# currentBaseBoard_v5.net
KiCad netlist of a schematic drawn in EAGLE
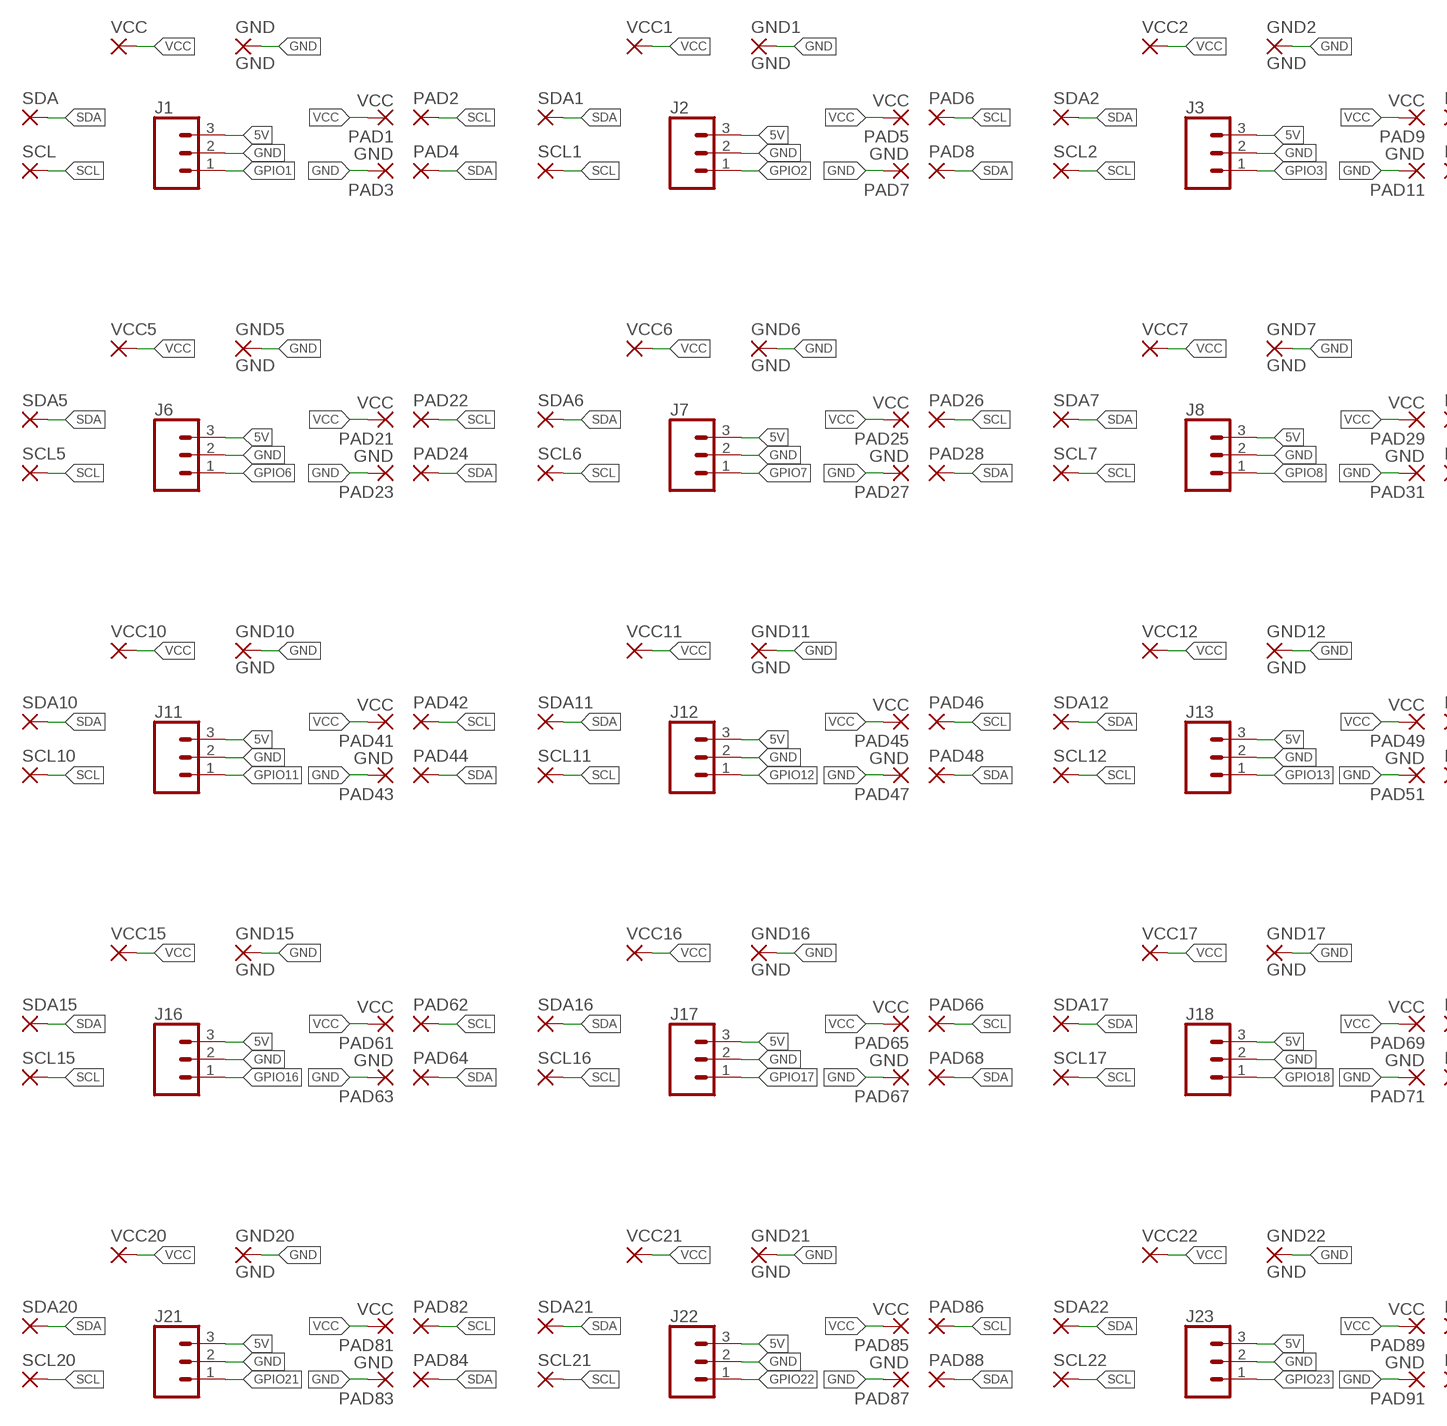
[diagram p0: schematic, sheet 1, part 1 of 2]
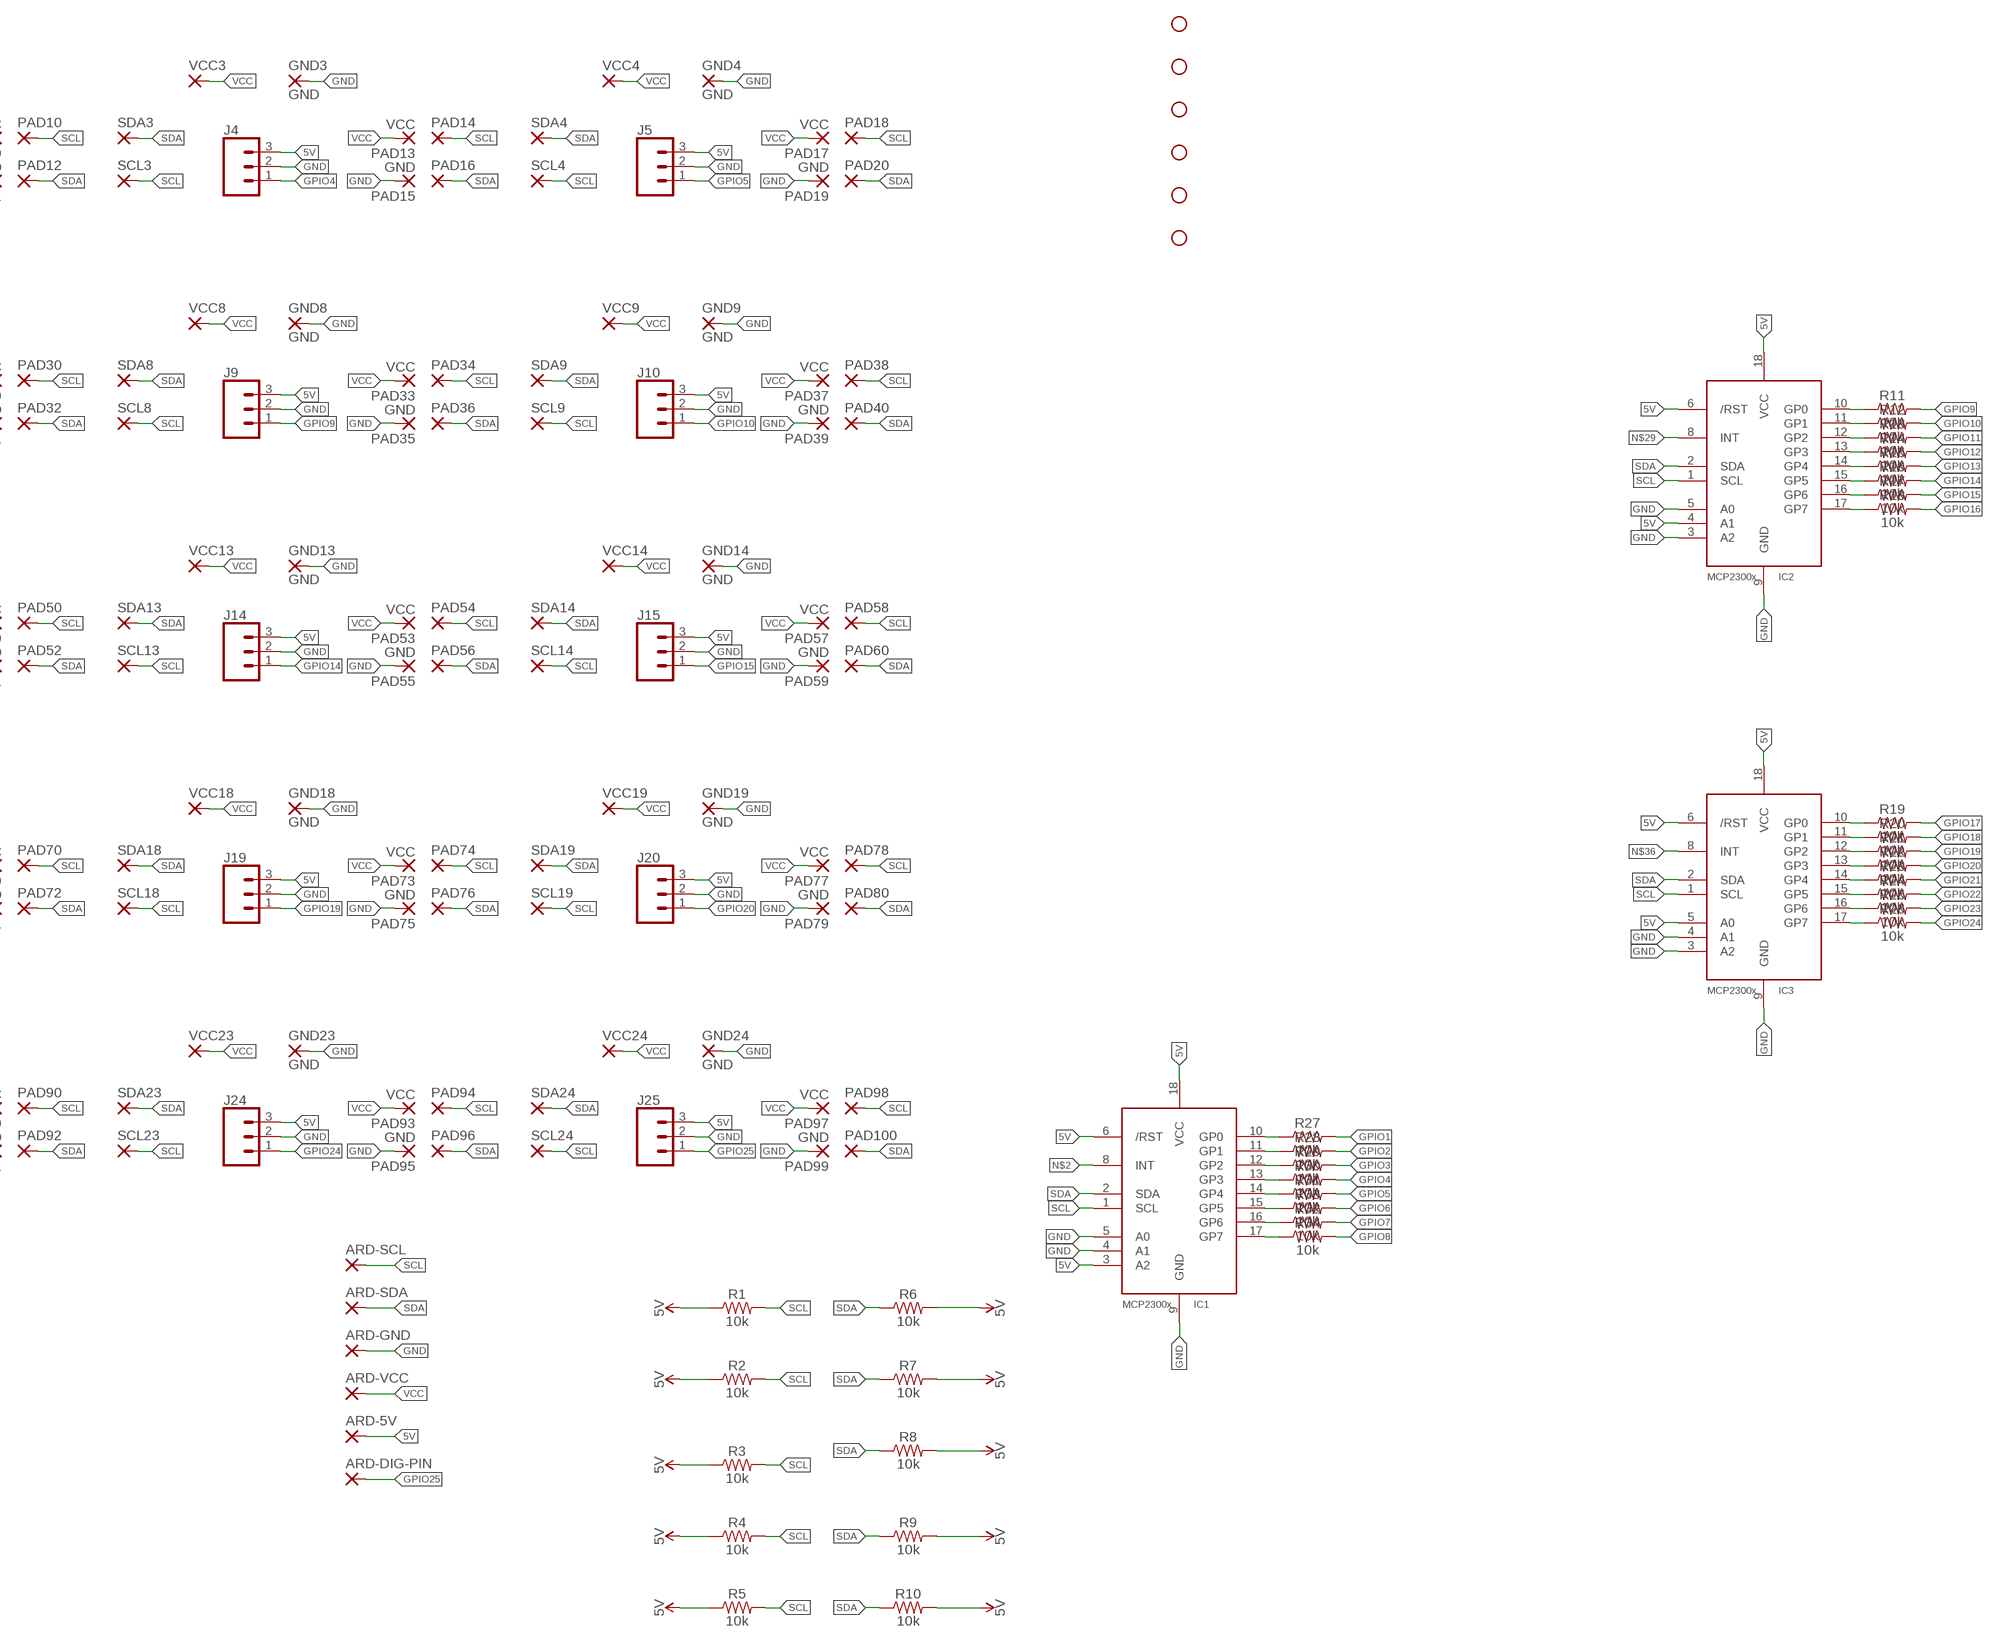
[diagram p1: schematic, sheet 1, part 2 of 2]

(export (version "E")
  (design (tool "Eeschema 10.0.6"))
  (components
    (comp (ref "ARD-5V")
      (value "2,15/1,0")
      (footprint "eagle-import:2,15_1,0")
      (libsource (lib "eagle-import") (part "2,15/1,0"))
    )
    (comp (ref "ARD-DIG-PIN")
      (value "2,15/1,0")
      (footprint "eagle-import:2,15_1,0")
      (libsource (lib "eagle-import") (part "2,15/1,0"))
    )
    (comp (ref "ARD-GND")
      (value "2,15/1,0")
      (footprint "eagle-import:2,15_1,0")
      (libsource (lib "eagle-import") (part "2,15/1,0"))
    )
    (comp (ref "ARD-SCL")
      (value "2,15/1,0")
      (footprint "eagle-import:2,15_1,0")
      (libsource (lib "eagle-import") (part "2,15/1,0"))
    )
    (comp (ref "ARD-SDA")
      (value "2,15/1,0")
      (footprint "eagle-import:2,15_1,0")
      (libsource (lib "eagle-import") (part "2,15/1,0"))
    )
    (comp (ref "ARD-VCC")
      (value "2,15/1,0")
      (footprint "eagle-import:2,15_1,0")
      (libsource (lib "eagle-import") (part "2,15/1,0"))
    )
    (comp (ref "GND")
      (value "GND")
      (footprint "eagle-import:2,15_1,0")
      (libsource (lib "eagle-import") (part "2,15/1,0"))
    )
    (comp (ref "GND1")
      (value "GND")
      (footprint "eagle-import:2,15_1,0")
      (libsource (lib "eagle-import") (part "2,15/1,0"))
    )
    (comp (ref "GND2")
      (value "GND")
      (footprint "eagle-import:2,15_1,0")
      (libsource (lib "eagle-import") (part "2,15/1,0"))
    )
    (comp (ref "GND3")
      (value "GND")
      (footprint "eagle-import:2,15_1,0")
      (libsource (lib "eagle-import") (part "2,15/1,0"))
    )
    (comp (ref "GND4")
      (value "GND")
      (footprint "eagle-import:2,15_1,0")
      (libsource (lib "eagle-import") (part "2,15/1,0"))
    )
    (comp (ref "GND5")
      (value "GND")
      (footprint "eagle-import:2,15_1,0")
      (libsource (lib "eagle-import") (part "2,15/1,0"))
    )
    (comp (ref "GND6")
      (value "GND")
      (footprint "eagle-import:2,15_1,0")
      (libsource (lib "eagle-import") (part "2,15/1,0"))
    )
    (comp (ref "GND7")
      (value "GND")
      (footprint "eagle-import:2,15_1,0")
      (libsource (lib "eagle-import") (part "2,15/1,0"))
    )
    (comp (ref "GND8")
      (value "GND")
      (footprint "eagle-import:2,15_1,0")
      (libsource (lib "eagle-import") (part "2,15/1,0"))
    )
    (comp (ref "GND9")
      (value "GND")
      (footprint "eagle-import:2,15_1,0")
      (libsource (lib "eagle-import") (part "2,15/1,0"))
    )
    (comp (ref "GND10")
      (value "GND")
      (footprint "eagle-import:2,15_1,0")
      (libsource (lib "eagle-import") (part "2,15/1,0"))
    )
    (comp (ref "GND11")
      (value "GND")
      (footprint "eagle-import:2,15_1,0")
      (libsource (lib "eagle-import") (part "2,15/1,0"))
    )
    (comp (ref "GND12")
      (value "GND")
      (footprint "eagle-import:2,15_1,0")
      (libsource (lib "eagle-import") (part "2,15/1,0"))
    )
    (comp (ref "GND13")
      (value "GND")
      (footprint "eagle-import:2,15_1,0")
      (libsource (lib "eagle-import") (part "2,15/1,0"))
    )
    (comp (ref "GND14")
      (value "GND")
      (footprint "eagle-import:2,15_1,0")
      (libsource (lib "eagle-import") (part "2,15/1,0"))
    )
    (comp (ref "GND15")
      (value "GND")
      (footprint "eagle-import:2,15_1,0")
      (libsource (lib "eagle-import") (part "2,15/1,0"))
    )
    (comp (ref "GND16")
      (value "GND")
      (footprint "eagle-import:2,15_1,0")
      (libsource (lib "eagle-import") (part "2,15/1,0"))
    )
    (comp (ref "GND17")
      (value "GND")
      (footprint "eagle-import:2,15_1,0")
      (libsource (lib "eagle-import") (part "2,15/1,0"))
    )
    (comp (ref "GND18")
      (value "GND")
      (footprint "eagle-import:2,15_1,0")
      (libsource (lib "eagle-import") (part "2,15/1,0"))
    )
    (comp (ref "GND19")
      (value "GND")
      (footprint "eagle-import:2,15_1,0")
      (libsource (lib "eagle-import") (part "2,15/1,0"))
    )
    (comp (ref "GND20")
      (value "GND")
      (footprint "eagle-import:2,15_1,0")
      (libsource (lib "eagle-import") (part "2,15/1,0"))
    )
    (comp (ref "GND21")
      (value "GND")
      (footprint "eagle-import:2,15_1,0")
      (libsource (lib "eagle-import") (part "2,15/1,0"))
    )
    (comp (ref "GND22")
      (value "GND")
      (footprint "eagle-import:2,15_1,0")
      (libsource (lib "eagle-import") (part "2,15/1,0"))
    )
    (comp (ref "GND23")
      (value "GND")
      (footprint "eagle-import:2,15_1,0")
      (libsource (lib "eagle-import") (part "2,15/1,0"))
    )
    (comp (ref "GND24")
      (value "GND")
      (footprint "eagle-import:2,15_1,0")
      (libsource (lib "eagle-import") (part "2,15/1,0"))
    )
    (comp (ref "H1")
      (value "STAND-OFF")
      (footprint "eagle-import:STAND-OFF")
      (libsource (lib "eagle-import") (part "STAND-OFF"))
    )
    (comp (ref "H2")
      (value "STAND-OFF")
      (footprint "eagle-import:STAND-OFF")
      (libsource (lib "eagle-import") (part "STAND-OFF"))
    )
    (comp (ref "H3")
      (value "STAND-OFF")
      (footprint "eagle-import:STAND-OFF")
      (libsource (lib "eagle-import") (part "STAND-OFF"))
    )
    (comp (ref "H4")
      (value "STAND-OFF")
      (footprint "eagle-import:STAND-OFF")
      (libsource (lib "eagle-import") (part "STAND-OFF"))
    )
    (comp (ref "H5")
      (value "STAND-OFF")
      (footprint "eagle-import:STAND-OFF")
      (libsource (lib "eagle-import") (part "STAND-OFF"))
    )
    (comp (ref "H6")
      (value "STAND-OFF")
      (footprint "eagle-import:STAND-OFF")
      (libsource (lib "eagle-import") (part "STAND-OFF"))
    )
    (comp (ref "IC1")
      (value "MCP23008/P")
      (footprint "eagle-import:DIL18")
      (libsource (lib "eagle-import") (part "MCP23008/P"))
    )
    (comp (ref "IC2")
      (value "MCP23008/P")
      (footprint "eagle-import:DIL18")
      (libsource (lib "eagle-import") (part "MCP23008/P"))
    )
    (comp (ref "IC3")
      (value "MCP23008/P")
      (footprint "eagle-import:DIL18")
      (libsource (lib "eagle-import") (part "MCP23008/P"))
    )
    (comp (ref "J1")
      (value "CONN_03")
      (footprint "eagle-import:1X03")
      (libsource (lib "eagle-import") (part "CONN_03"))
    )
    (comp (ref "J2")
      (value "CONN_03")
      (footprint "eagle-import:1X03")
      (libsource (lib "eagle-import") (part "CONN_03"))
    )
    (comp (ref "J3")
      (value "CONN_03")
      (footprint "eagle-import:1X03")
      (libsource (lib "eagle-import") (part "CONN_03"))
    )
    (comp (ref "J4")
      (value "CONN_03")
      (footprint "eagle-import:1X03")
      (libsource (lib "eagle-import") (part "CONN_03"))
    )
    (comp (ref "J5")
      (value "CONN_03")
      (footprint "eagle-import:1X03")
      (libsource (lib "eagle-import") (part "CONN_03"))
    )
    (comp (ref "J6")
      (value "CONN_03")
      (footprint "eagle-import:1X03")
      (libsource (lib "eagle-import") (part "CONN_03"))
    )
    (comp (ref "J7")
      (value "CONN_03")
      (footprint "eagle-import:1X03")
      (libsource (lib "eagle-import") (part "CONN_03"))
    )
    (comp (ref "J8")
      (value "CONN_03")
      (footprint "eagle-import:1X03")
      (libsource (lib "eagle-import") (part "CONN_03"))
    )
    (comp (ref "J9")
      (value "CONN_03")
      (footprint "eagle-import:1X03")
      (libsource (lib "eagle-import") (part "CONN_03"))
    )
    (comp (ref "J10")
      (value "CONN_03")
      (footprint "eagle-import:1X03")
      (libsource (lib "eagle-import") (part "CONN_03"))
    )
    (comp (ref "J11")
      (value "CONN_03")
      (footprint "eagle-import:1X03")
      (libsource (lib "eagle-import") (part "CONN_03"))
    )
    (comp (ref "J12")
      (value "CONN_03")
      (footprint "eagle-import:1X03")
      (libsource (lib "eagle-import") (part "CONN_03"))
    )
    (comp (ref "J13")
      (value "CONN_03")
      (footprint "eagle-import:1X03")
      (libsource (lib "eagle-import") (part "CONN_03"))
    )
    (comp (ref "J14")
      (value "CONN_03")
      (footprint "eagle-import:1X03")
      (libsource (lib "eagle-import") (part "CONN_03"))
    )
    (comp (ref "J15")
      (value "CONN_03")
      (footprint "eagle-import:1X03")
      (libsource (lib "eagle-import") (part "CONN_03"))
    )
    (comp (ref "J16")
      (value "CONN_03")
      (footprint "eagle-import:1X03")
      (libsource (lib "eagle-import") (part "CONN_03"))
    )
    (comp (ref "J17")
      (value "CONN_03")
      (footprint "eagle-import:1X03")
      (libsource (lib "eagle-import") (part "CONN_03"))
    )
    (comp (ref "J18")
      (value "CONN_03")
      (footprint "eagle-import:1X03")
      (libsource (lib "eagle-import") (part "CONN_03"))
    )
    (comp (ref "J19")
      (value "CONN_03")
      (footprint "eagle-import:1X03")
      (libsource (lib "eagle-import") (part "CONN_03"))
    )
    (comp (ref "J20")
      (value "CONN_03")
      (footprint "eagle-import:1X03")
      (libsource (lib "eagle-import") (part "CONN_03"))
    )
    (comp (ref "J21")
      (value "CONN_03")
      (footprint "eagle-import:1X03")
      (libsource (lib "eagle-import") (part "CONN_03"))
    )
    (comp (ref "J22")
      (value "CONN_03")
      (footprint "eagle-import:1X03")
      (libsource (lib "eagle-import") (part "CONN_03"))
    )
    (comp (ref "J23")
      (value "CONN_03")
      (footprint "eagle-import:1X03")
      (libsource (lib "eagle-import") (part "CONN_03"))
    )
    (comp (ref "J24")
      (value "CONN_03")
      (footprint "eagle-import:1X03")
      (libsource (lib "eagle-import") (part "CONN_03"))
    )
    (comp (ref "J25")
      (value "CONN_03")
      (footprint "eagle-import:1X03")
      (libsource (lib "eagle-import") (part "CONN_03"))
    )
    (comp (ref "PAD1")
      (value "VCC")
      (footprint "eagle-import:2,15_1,0")
      (libsource (lib "eagle-import") (part "2,15/1,0"))
    )
    (comp (ref "PAD2")
      (value "2,15/1,0")
      (footprint "eagle-import:2,15_1,0")
      (libsource (lib "eagle-import") (part "2,15/1,0"))
    )
    (comp (ref "PAD3")
      (value "GND")
      (footprint "eagle-import:2,15_1,0")
      (libsource (lib "eagle-import") (part "2,15/1,0"))
    )
    (comp (ref "PAD4")
      (value "2,15/1,0")
      (footprint "eagle-import:2,15_1,0")
      (libsource (lib "eagle-import") (part "2,15/1,0"))
    )
    (comp (ref "PAD5")
      (value "VCC")
      (footprint "eagle-import:2,15_1,0")
      (libsource (lib "eagle-import") (part "2,15/1,0"))
    )
    (comp (ref "PAD6")
      (value "2,15/1,0")
      (footprint "eagle-import:2,15_1,0")
      (libsource (lib "eagle-import") (part "2,15/1,0"))
    )
    (comp (ref "PAD7")
      (value "GND")
      (footprint "eagle-import:2,15_1,0")
      (libsource (lib "eagle-import") (part "2,15/1,0"))
    )
    (comp (ref "PAD8")
      (value "2,15/1,0")
      (footprint "eagle-import:2,15_1,0")
      (libsource (lib "eagle-import") (part "2,15/1,0"))
    )
    (comp (ref "PAD9")
      (value "VCC")
      (footprint "eagle-import:2,15_1,0")
      (libsource (lib "eagle-import") (part "2,15/1,0"))
    )
    (comp (ref "PAD10")
      (value "2,15/1,0")
      (footprint "eagle-import:2,15_1,0")
      (libsource (lib "eagle-import") (part "2,15/1,0"))
    )
    (comp (ref "PAD11")
      (value "GND")
      (footprint "eagle-import:2,15_1,0")
      (libsource (lib "eagle-import") (part "2,15/1,0"))
    )
    (comp (ref "PAD12")
      (value "2,15/1,0")
      (footprint "eagle-import:2,15_1,0")
      (libsource (lib "eagle-import") (part "2,15/1,0"))
    )
    (comp (ref "PAD13")
      (value "VCC")
      (footprint "eagle-import:2,15_1,0")
      (libsource (lib "eagle-import") (part "2,15/1,0"))
    )
    (comp (ref "PAD14")
      (value "2,15/1,0")
      (footprint "eagle-import:2,15_1,0")
      (libsource (lib "eagle-import") (part "2,15/1,0"))
    )
    (comp (ref "PAD15")
      (value "GND")
      (footprint "eagle-import:2,15_1,0")
      (libsource (lib "eagle-import") (part "2,15/1,0"))
    )
    (comp (ref "PAD16")
      (value "2,15/1,0")
      (footprint "eagle-import:2,15_1,0")
      (libsource (lib "eagle-import") (part "2,15/1,0"))
    )
    (comp (ref "PAD17")
      (value "VCC")
      (footprint "eagle-import:2,15_1,0")
      (libsource (lib "eagle-import") (part "2,15/1,0"))
    )
    (comp (ref "PAD18")
      (value "2,15/1,0")
      (footprint "eagle-import:2,15_1,0")
      (libsource (lib "eagle-import") (part "2,15/1,0"))
    )
    (comp (ref "PAD19")
      (value "GND")
      (footprint "eagle-import:2,15_1,0")
      (libsource (lib "eagle-import") (part "2,15/1,0"))
    )
    (comp (ref "PAD20")
      (value "2,15/1,0")
      (footprint "eagle-import:2,15_1,0")
      (libsource (lib "eagle-import") (part "2,15/1,0"))
    )
    (comp (ref "PAD21")
      (value "VCC")
      (footprint "eagle-import:2,15_1,0")
      (libsource (lib "eagle-import") (part "2,15/1,0"))
    )
    (comp (ref "PAD22")
      (value "2,15/1,0")
      (footprint "eagle-import:2,15_1,0")
      (libsource (lib "eagle-import") (part "2,15/1,0"))
    )
    (comp (ref "PAD23")
      (value "GND")
      (footprint "eagle-import:2,15_1,0")
      (libsource (lib "eagle-import") (part "2,15/1,0"))
    )
    (comp (ref "PAD24")
      (value "2,15/1,0")
      (footprint "eagle-import:2,15_1,0")
      (libsource (lib "eagle-import") (part "2,15/1,0"))
    )
    (comp (ref "PAD25")
      (value "VCC")
      (footprint "eagle-import:2,15_1,0")
      (libsource (lib "eagle-import") (part "2,15/1,0"))
    )
    (comp (ref "PAD26")
      (value "2,15/1,0")
      (footprint "eagle-import:2,15_1,0")
      (libsource (lib "eagle-import") (part "2,15/1,0"))
    )
    (comp (ref "PAD27")
      (value "GND")
      (footprint "eagle-import:2,15_1,0")
      (libsource (lib "eagle-import") (part "2,15/1,0"))
    )
    (comp (ref "PAD28")
      (value "2,15/1,0")
      (footprint "eagle-import:2,15_1,0")
      (libsource (lib "eagle-import") (part "2,15/1,0"))
    )
    (comp (ref "PAD29")
      (value "VCC")
      (footprint "eagle-import:2,15_1,0")
      (libsource (lib "eagle-import") (part "2,15/1,0"))
    )
    (comp (ref "PAD30")
      (value "2,15/1,0")
      (footprint "eagle-import:2,15_1,0")
      (libsource (lib "eagle-import") (part "2,15/1,0"))
    )
    (comp (ref "PAD31")
      (value "GND")
      (footprint "eagle-import:2,15_1,0")
      (libsource (lib "eagle-import") (part "2,15/1,0"))
    )
    (comp (ref "PAD32")
      (value "2,15/1,0")
      (footprint "eagle-import:2,15_1,0")
      (libsource (lib "eagle-import") (part "2,15/1,0"))
    )
    (comp (ref "PAD33")
      (value "VCC")
      (footprint "eagle-import:2,15_1,0")
      (libsource (lib "eagle-import") (part "2,15/1,0"))
    )
    (comp (ref "PAD34")
      (value "2,15/1,0")
      (footprint "eagle-import:2,15_1,0")
      (libsource (lib "eagle-import") (part "2,15/1,0"))
    )
    (comp (ref "PAD35")
      (value "GND")
      (footprint "eagle-import:2,15_1,0")
      (libsource (lib "eagle-import") (part "2,15/1,0"))
    )
    (comp (ref "PAD36")
      (value "2,15/1,0")
      (footprint "eagle-import:2,15_1,0")
      (libsource (lib "eagle-import") (part "2,15/1,0"))
    )
    (comp (ref "PAD37")
      (value "VCC")
      (footprint "eagle-import:2,15_1,0")
      (libsource (lib "eagle-import") (part "2,15/1,0"))
    )
    (comp (ref "PAD38")
      (value "2,15/1,0")
      (footprint "eagle-import:2,15_1,0")
      (libsource (lib "eagle-import") (part "2,15/1,0"))
    )
    (comp (ref "PAD39")
      (value "GND")
      (footprint "eagle-import:2,15_1,0")
      (libsource (lib "eagle-import") (part "2,15/1,0"))
    )
    (comp (ref "PAD40")
      (value "2,15/1,0")
      (footprint "eagle-import:2,15_1,0")
      (libsource (lib "eagle-import") (part "2,15/1,0"))
    )
    (comp (ref "PAD41")
      (value "VCC")
      (footprint "eagle-import:2,15_1,0")
      (libsource (lib "eagle-import") (part "2,15/1,0"))
    )
    (comp (ref "PAD42")
      (value "2,15/1,0")
      (footprint "eagle-import:2,15_1,0")
      (libsource (lib "eagle-import") (part "2,15/1,0"))
    )
    (comp (ref "PAD43")
      (value "GND")
      (footprint "eagle-import:2,15_1,0")
      (libsource (lib "eagle-import") (part "2,15/1,0"))
    )
    (comp (ref "PAD44")
      (value "2,15/1,0")
      (footprint "eagle-import:2,15_1,0")
      (libsource (lib "eagle-import") (part "2,15/1,0"))
    )
    (comp (ref "PAD45")
      (value "VCC")
      (footprint "eagle-import:2,15_1,0")
      (libsource (lib "eagle-import") (part "2,15/1,0"))
    )
    (comp (ref "PAD46")
      (value "2,15/1,0")
      (footprint "eagle-import:2,15_1,0")
      (libsource (lib "eagle-import") (part "2,15/1,0"))
    )
    (comp (ref "PAD47")
      (value "GND")
      (footprint "eagle-import:2,15_1,0")
      (libsource (lib "eagle-import") (part "2,15/1,0"))
    )
    (comp (ref "PAD48")
      (value "2,15/1,0")
      (footprint "eagle-import:2,15_1,0")
      (libsource (lib "eagle-import") (part "2,15/1,0"))
    )
    (comp (ref "PAD49")
      (value "VCC")
      (footprint "eagle-import:2,15_1,0")
      (libsource (lib "eagle-import") (part "2,15/1,0"))
    )
    (comp (ref "PAD50")
      (value "2,15/1,0")
      (footprint "eagle-import:2,15_1,0")
      (libsource (lib "eagle-import") (part "2,15/1,0"))
    )
    (comp (ref "PAD51")
      (value "GND")
      (footprint "eagle-import:2,15_1,0")
      (libsource (lib "eagle-import") (part "2,15/1,0"))
    )
    (comp (ref "PAD52")
      (value "2,15/1,0")
      (footprint "eagle-import:2,15_1,0")
      (libsource (lib "eagle-import") (part "2,15/1,0"))
    )
    (comp (ref "PAD53")
      (value "VCC")
      (footprint "eagle-import:2,15_1,0")
      (libsource (lib "eagle-import") (part "2,15/1,0"))
    )
    (comp (ref "PAD54")
      (value "2,15/1,0")
      (footprint "eagle-import:2,15_1,0")
      (libsource (lib "eagle-import") (part "2,15/1,0"))
    )
    (comp (ref "PAD55")
      (value "GND")
      (footprint "eagle-import:2,15_1,0")
      (libsource (lib "eagle-import") (part "2,15/1,0"))
    )
    (comp (ref "PAD56")
      (value "2,15/1,0")
      (footprint "eagle-import:2,15_1,0")
      (libsource (lib "eagle-import") (part "2,15/1,0"))
    )
    (comp (ref "PAD57")
      (value "VCC")
      (footprint "eagle-import:2,15_1,0")
      (libsource (lib "eagle-import") (part "2,15/1,0"))
    )
    (comp (ref "PAD58")
      (value "2,15/1,0")
      (footprint "eagle-import:2,15_1,0")
      (libsource (lib "eagle-import") (part "2,15/1,0"))
    )
    (comp (ref "PAD59")
      (value "GND")
      (footprint "eagle-import:2,15_1,0")
      (libsource (lib "eagle-import") (part "2,15/1,0"))
    )
    (comp (ref "PAD60")
      (value "2,15/1,0")
      (footprint "eagle-import:2,15_1,0")
      (libsource (lib "eagle-import") (part "2,15/1,0"))
    )
    (comp (ref "PAD61")
      (value "VCC")
      (footprint "eagle-import:2,15_1,0")
      (libsource (lib "eagle-import") (part "2,15/1,0"))
    )
    (comp (ref "PAD62")
      (value "2,15/1,0")
      (footprint "eagle-import:2,15_1,0")
      (libsource (lib "eagle-import") (part "2,15/1,0"))
    )
    (comp (ref "PAD63")
      (value "GND")
      (footprint "eagle-import:2,15_1,0")
      (libsource (lib "eagle-import") (part "2,15/1,0"))
    )
    (comp (ref "PAD64")
      (value "2,15/1,0")
      (footprint "eagle-import:2,15_1,0")
      (libsource (lib "eagle-import") (part "2,15/1,0"))
    )
    (comp (ref "PAD65")
      (value "VCC")
      (footprint "eagle-import:2,15_1,0")
      (libsource (lib "eagle-import") (part "2,15/1,0"))
    )
    (comp (ref "PAD66")
      (value "2,15/1,0")
      (footprint "eagle-import:2,15_1,0")
      (libsource (lib "eagle-import") (part "2,15/1,0"))
    )
    (comp (ref "PAD67")
      (value "GND")
      (footprint "eagle-import:2,15_1,0")
      (libsource (lib "eagle-import") (part "2,15/1,0"))
    )
    (comp (ref "PAD68")
      (value "2,15/1,0")
      (footprint "eagle-import:2,15_1,0")
      (libsource (lib "eagle-import") (part "2,15/1,0"))
    )
    (comp (ref "PAD69")
      (value "VCC")
      (footprint "eagle-import:2,15_1,0")
      (libsource (lib "eagle-import") (part "2,15/1,0"))
    )
    (comp (ref "PAD70")
      (value "2,15/1,0")
      (footprint "eagle-import:2,15_1,0")
      (libsource (lib "eagle-import") (part "2,15/1,0"))
    )
    (comp (ref "PAD71")
      (value "GND")
      (footprint "eagle-import:2,15_1,0")
      (libsource (lib "eagle-import") (part "2,15/1,0"))
    )
    (comp (ref "PAD72")
      (value "2,15/1,0")
      (footprint "eagle-import:2,15_1,0")
      (libsource (lib "eagle-import") (part "2,15/1,0"))
    )
    (comp (ref "PAD73")
      (value "VCC")
      (footprint "eagle-import:2,15_1,0")
      (libsource (lib "eagle-import") (part "2,15/1,0"))
    )
    (comp (ref "PAD74")
      (value "2,15/1,0")
      (footprint "eagle-import:2,15_1,0")
      (libsource (lib "eagle-import") (part "2,15/1,0"))
    )
    (comp (ref "PAD75")
      (value "GND")
      (footprint "eagle-import:2,15_1,0")
      (libsource (lib "eagle-import") (part "2,15/1,0"))
    )
    (comp (ref "PAD76")
      (value "2,15/1,0")
      (footprint "eagle-import:2,15_1,0")
      (libsource (lib "eagle-import") (part "2,15/1,0"))
    )
    (comp (ref "PAD77")
      (value "VCC")
      (footprint "eagle-import:2,15_1,0")
      (libsource (lib "eagle-import") (part "2,15/1,0"))
    )
    (comp (ref "PAD78")
      (value "2,15/1,0")
      (footprint "eagle-import:2,15_1,0")
      (libsource (lib "eagle-import") (part "2,15/1,0"))
    )
    (comp (ref "PAD79")
      (value "GND")
      (footprint "eagle-import:2,15_1,0")
      (libsource (lib "eagle-import") (part "2,15/1,0"))
    )
    (comp (ref "PAD80")
      (value "2,15/1,0")
      (footprint "eagle-import:2,15_1,0")
      (libsource (lib "eagle-import") (part "2,15/1,0"))
    )
    (comp (ref "PAD81")
      (value "VCC")
      (footprint "eagle-import:2,15_1,0")
      (libsource (lib "eagle-import") (part "2,15/1,0"))
    )
    (comp (ref "PAD82")
      (value "2,15/1,0")
      (footprint "eagle-import:2,15_1,0")
      (libsource (lib "eagle-import") (part "2,15/1,0"))
    )
    (comp (ref "PAD83")
      (value "GND")
      (footprint "eagle-import:2,15_1,0")
      (libsource (lib "eagle-import") (part "2,15/1,0"))
    )
    (comp (ref "PAD84")
      (value "2,15/1,0")
      (footprint "eagle-import:2,15_1,0")
      (libsource (lib "eagle-import") (part "2,15/1,0"))
    )
    (comp (ref "PAD85")
      (value "VCC")
      (footprint "eagle-import:2,15_1,0")
      (libsource (lib "eagle-import") (part "2,15/1,0"))
    )
    (comp (ref "PAD86")
      (value "2,15/1,0")
      (footprint "eagle-import:2,15_1,0")
      (libsource (lib "eagle-import") (part "2,15/1,0"))
    )
    (comp (ref "PAD87")
      (value "GND")
      (footprint "eagle-import:2,15_1,0")
      (libsource (lib "eagle-import") (part "2,15/1,0"))
    )
    (comp (ref "PAD88")
      (value "2,15/1,0")
      (footprint "eagle-import:2,15_1,0")
      (libsource (lib "eagle-import") (part "2,15/1,0"))
    )
    (comp (ref "PAD89")
      (value "VCC")
      (footprint "eagle-import:2,15_1,0")
      (libsource (lib "eagle-import") (part "2,15/1,0"))
    )
    (comp (ref "PAD90")
      (value "2,15/1,0")
      (footprint "eagle-import:2,15_1,0")
      (libsource (lib "eagle-import") (part "2,15/1,0"))
    )
    (comp (ref "PAD91")
      (value "GND")
      (footprint "eagle-import:2,15_1,0")
      (libsource (lib "eagle-import") (part "2,15/1,0"))
    )
    (comp (ref "PAD92")
      (value "2,15/1,0")
      (footprint "eagle-import:2,15_1,0")
      (libsource (lib "eagle-import") (part "2,15/1,0"))
    )
    (comp (ref "PAD93")
      (value "VCC")
      (footprint "eagle-import:2,15_1,0")
      (libsource (lib "eagle-import") (part "2,15/1,0"))
    )
    (comp (ref "PAD94")
      (value "2,15/1,0")
      (footprint "eagle-import:2,15_1,0")
      (libsource (lib "eagle-import") (part "2,15/1,0"))
    )
    (comp (ref "PAD95")
      (value "GND")
      (footprint "eagle-import:2,15_1,0")
      (libsource (lib "eagle-import") (part "2,15/1,0"))
    )
    (comp (ref "PAD96")
      (value "2,15/1,0")
      (footprint "eagle-import:2,15_1,0")
      (libsource (lib "eagle-import") (part "2,15/1,0"))
    )
    (comp (ref "PAD97")
      (value "VCC")
      (footprint "eagle-import:2,15_1,0")
      (libsource (lib "eagle-import") (part "2,15/1,0"))
    )
    (comp (ref "PAD98")
      (value "2,15/1,0")
      (footprint "eagle-import:2,15_1,0")
      (libsource (lib "eagle-import") (part "2,15/1,0"))
    )
    (comp (ref "PAD99")
      (value "GND")
      (footprint "eagle-import:2,15_1,0")
      (libsource (lib "eagle-import") (part "2,15/1,0"))
    )
    (comp (ref "PAD100")
      (value "2,15/1,0")
      (footprint "eagle-import:2,15_1,0")
      (libsource (lib "eagle-import") (part "2,15/1,0"))
    )
    (comp (ref "R1")
      (value "10k")
      (footprint "eagle-import:AXIAL-0.3")
      (libsource (lib "eagle-import") (part "10KOHM-HORIZ-1/4W-1%"))
    )
    (comp (ref "R2")
      (value "10k")
      (footprint "eagle-import:AXIAL-0.3")
      (libsource (lib "eagle-import") (part "10KOHM-HORIZ-1/4W-1%"))
    )
    (comp (ref "R3")
      (value "10k")
      (footprint "eagle-import:AXIAL-0.3")
      (libsource (lib "eagle-import") (part "10KOHM-HORIZ-1/4W-1%"))
    )
    (comp (ref "R4")
      (value "10k")
      (footprint "eagle-import:AXIAL-0.3")
      (libsource (lib "eagle-import") (part "10KOHM-HORIZ-1/4W-1%"))
    )
    (comp (ref "R5")
      (value "10k")
      (footprint "eagle-import:AXIAL-0.3")
      (libsource (lib "eagle-import") (part "10KOHM-HORIZ-1/4W-1%"))
    )
    (comp (ref "R6")
      (value "10k")
      (footprint "eagle-import:AXIAL-0.3")
      (libsource (lib "eagle-import") (part "10KOHM-HORIZ-1/4W-1%"))
    )
    (comp (ref "R7")
      (value "10k")
      (footprint "eagle-import:AXIAL-0.3")
      (libsource (lib "eagle-import") (part "10KOHM-HORIZ-1/4W-1%"))
    )
    (comp (ref "R8")
      (value "10k")
      (footprint "eagle-import:AXIAL-0.3")
      (libsource (lib "eagle-import") (part "10KOHM-HORIZ-1/4W-1%"))
    )
    (comp (ref "R9")
      (value "10k")
      (footprint "eagle-import:AXIAL-0.3")
      (libsource (lib "eagle-import") (part "10KOHM-HORIZ-1/4W-1%"))
    )
    (comp (ref "R10")
      (value "10k")
      (footprint "eagle-import:AXIAL-0.3")
      (libsource (lib "eagle-import") (part "10KOHM-HORIZ-1/4W-1%"))
    )
    (comp (ref "R11")
      (value "10k")
      (footprint "eagle-import:AXIAL-0.3")
      (libsource (lib "eagle-import") (part "10KOHM-HORIZ-1/6W-5%"))
    )
    (comp (ref "R12")
      (value "10k")
      (footprint "eagle-import:AXIAL-0.3")
      (libsource (lib "eagle-import") (part "10KOHM-HORIZ-1/6W-5%"))
    )
    (comp (ref "R13")
      (value "10k")
      (footprint "eagle-import:AXIAL-0.3")
      (libsource (lib "eagle-import") (part "10KOHM-HORIZ-1/6W-5%"))
    )
    (comp (ref "R14")
      (value "10k")
      (footprint "eagle-import:AXIAL-0.3")
      (libsource (lib "eagle-import") (part "10KOHM-HORIZ-1/6W-5%"))
    )
    (comp (ref "R15")
      (value "10k")
      (footprint "eagle-import:AXIAL-0.3")
      (libsource (lib "eagle-import") (part "10KOHM-HORIZ-1/6W-5%"))
    )
    (comp (ref "R16")
      (value "10k")
      (footprint "eagle-import:AXIAL-0.3")
      (libsource (lib "eagle-import") (part "10KOHM-HORIZ-1/6W-5%"))
    )
    (comp (ref "R17")
      (value "10k")
      (footprint "eagle-import:AXIAL-0.3")
      (libsource (lib "eagle-import") (part "10KOHM-HORIZ-1/6W-5%"))
    )
    (comp (ref "R18")
      (value "10k")
      (footprint "eagle-import:AXIAL-0.3")
      (libsource (lib "eagle-import") (part "10KOHM-HORIZ-1/6W-5%"))
    )
    (comp (ref "R19")
      (value "10k")
      (footprint "eagle-import:AXIAL-0.3")
      (libsource (lib "eagle-import") (part "10KOHM-HORIZ-1/6W-5%"))
    )
    (comp (ref "R20")
      (value "10k")
      (footprint "eagle-import:AXIAL-0.3")
      (libsource (lib "eagle-import") (part "10KOHM-HORIZ-1/6W-5%"))
    )
    (comp (ref "R21")
      (value "10k")
      (footprint "eagle-import:AXIAL-0.3")
      (libsource (lib "eagle-import") (part "10KOHM-HORIZ-1/6W-5%"))
    )
    (comp (ref "R22")
      (value "10k")
      (footprint "eagle-import:AXIAL-0.3")
      (libsource (lib "eagle-import") (part "10KOHM-HORIZ-1/6W-5%"))
    )
    (comp (ref "R23")
      (value "10k")
      (footprint "eagle-import:AXIAL-0.3")
      (libsource (lib "eagle-import") (part "10KOHM-HORIZ-1/6W-5%"))
    )
    (comp (ref "R24")
      (value "10k")
      (footprint "eagle-import:AXIAL-0.3")
      (libsource (lib "eagle-import") (part "10KOHM-HORIZ-1/6W-5%"))
    )
    (comp (ref "R25")
      (value "10k")
      (footprint "eagle-import:AXIAL-0.3")
      (libsource (lib "eagle-import") (part "10KOHM-HORIZ-1/6W-5%"))
    )
    (comp (ref "R26")
      (value "10k")
      (footprint "eagle-import:AXIAL-0.3")
      (libsource (lib "eagle-import") (part "10KOHM-HORIZ-1/6W-5%"))
    )
    (comp (ref "R27")
      (value "10k")
      (footprint "eagle-import:AXIAL-0.3")
      (libsource (lib "eagle-import") (part "10KOHM-HORIZ-1/6W-5%"))
    )
    (comp (ref "R28")
      (value "10k")
      (footprint "eagle-import:AXIAL-0.3")
      (libsource (lib "eagle-import") (part "10KOHM-HORIZ-1/6W-5%"))
    )
    (comp (ref "R29")
      (value "10k")
      (footprint "eagle-import:AXIAL-0.3")
      (libsource (lib "eagle-import") (part "10KOHM-HORIZ-1/6W-5%"))
    )
    (comp (ref "R30")
      (value "10k")
      (footprint "eagle-import:AXIAL-0.3")
      (libsource (lib "eagle-import") (part "10KOHM-HORIZ-1/6W-5%"))
    )
    (comp (ref "R31")
      (value "10k")
      (footprint "eagle-import:AXIAL-0.3")
      (libsource (lib "eagle-import") (part "10KOHM-HORIZ-1/6W-5%"))
    )
    (comp (ref "R32")
      (value "10k")
      (footprint "eagle-import:AXIAL-0.3")
      (libsource (lib "eagle-import") (part "10KOHM-HORIZ-1/6W-5%"))
    )
    (comp (ref "R33")
      (value "10k")
      (footprint "eagle-import:AXIAL-0.3")
      (libsource (lib "eagle-import") (part "10KOHM-HORIZ-1/6W-5%"))
    )
    (comp (ref "R34")
      (value "10k")
      (footprint "eagle-import:AXIAL-0.3")
      (libsource (lib "eagle-import") (part "10KOHM-HORIZ-1/6W-5%"))
    )
    (comp (ref "SCL")
      (value "2,15/1,0")
      (footprint "eagle-import:2,15_1,0")
      (libsource (lib "eagle-import") (part "2,15/1,0"))
    )
    (comp (ref "SCL1")
      (value "2,15/1,0")
      (footprint "eagle-import:2,15_1,0")
      (libsource (lib "eagle-import") (part "2,15/1,0"))
    )
    (comp (ref "SCL2")
      (value "2,15/1,0")
      (footprint "eagle-import:2,15_1,0")
      (libsource (lib "eagle-import") (part "2,15/1,0"))
    )
    (comp (ref "SCL3")
      (value "2,15/1,0")
      (footprint "eagle-import:2,15_1,0")
      (libsource (lib "eagle-import") (part "2,15/1,0"))
    )
    (comp (ref "SCL4")
      (value "2,15/1,0")
      (footprint "eagle-import:2,15_1,0")
      (libsource (lib "eagle-import") (part "2,15/1,0"))
    )
    (comp (ref "SCL5")
      (value "2,15/1,0")
      (footprint "eagle-import:2,15_1,0")
      (libsource (lib "eagle-import") (part "2,15/1,0"))
    )
    (comp (ref "SCL6")
      (value "2,15/1,0")
      (footprint "eagle-import:2,15_1,0")
      (libsource (lib "eagle-import") (part "2,15/1,0"))
    )
    (comp (ref "SCL7")
      (value "2,15/1,0")
      (footprint "eagle-import:2,15_1,0")
      (libsource (lib "eagle-import") (part "2,15/1,0"))
    )
    (comp (ref "SCL8")
      (value "2,15/1,0")
      (footprint "eagle-import:2,15_1,0")
      (libsource (lib "eagle-import") (part "2,15/1,0"))
    )
    (comp (ref "SCL9")
      (value "2,15/1,0")
      (footprint "eagle-import:2,15_1,0")
      (libsource (lib "eagle-import") (part "2,15/1,0"))
    )
    (comp (ref "SCL10")
      (value "2,15/1,0")
      (footprint "eagle-import:2,15_1,0")
      (libsource (lib "eagle-import") (part "2,15/1,0"))
    )
    (comp (ref "SCL11")
      (value "2,15/1,0")
      (footprint "eagle-import:2,15_1,0")
      (libsource (lib "eagle-import") (part "2,15/1,0"))
    )
    (comp (ref "SCL12")
      (value "2,15/1,0")
      (footprint "eagle-import:2,15_1,0")
      (libsource (lib "eagle-import") (part "2,15/1,0"))
    )
    (comp (ref "SCL13")
      (value "2,15/1,0")
      (footprint "eagle-import:2,15_1,0")
      (libsource (lib "eagle-import") (part "2,15/1,0"))
    )
    (comp (ref "SCL14")
      (value "2,15/1,0")
      (footprint "eagle-import:2,15_1,0")
      (libsource (lib "eagle-import") (part "2,15/1,0"))
    )
    (comp (ref "SCL15")
      (value "2,15/1,0")
      (footprint "eagle-import:2,15_1,0")
      (libsource (lib "eagle-import") (part "2,15/1,0"))
    )
    (comp (ref "SCL16")
      (value "2,15/1,0")
      (footprint "eagle-import:2,15_1,0")
      (libsource (lib "eagle-import") (part "2,15/1,0"))
    )
    (comp (ref "SCL17")
      (value "2,15/1,0")
      (footprint "eagle-import:2,15_1,0")
      (libsource (lib "eagle-import") (part "2,15/1,0"))
    )
    (comp (ref "SCL18")
      (value "2,15/1,0")
      (footprint "eagle-import:2,15_1,0")
      (libsource (lib "eagle-import") (part "2,15/1,0"))
    )
    (comp (ref "SCL19")
      (value "2,15/1,0")
      (footprint "eagle-import:2,15_1,0")
      (libsource (lib "eagle-import") (part "2,15/1,0"))
    )
    (comp (ref "SCL20")
      (value "2,15/1,0")
      (footprint "eagle-import:2,15_1,0")
      (libsource (lib "eagle-import") (part "2,15/1,0"))
    )
    (comp (ref "SCL21")
      (value "2,15/1,0")
      (footprint "eagle-import:2,15_1,0")
      (libsource (lib "eagle-import") (part "2,15/1,0"))
    )
    (comp (ref "SCL22")
      (value "2,15/1,0")
      (footprint "eagle-import:2,15_1,0")
      (libsource (lib "eagle-import") (part "2,15/1,0"))
    )
    (comp (ref "SCL23")
      (value "2,15/1,0")
      (footprint "eagle-import:2,15_1,0")
      (libsource (lib "eagle-import") (part "2,15/1,0"))
    )
    (comp (ref "SCL24")
      (value "2,15/1,0")
      (footprint "eagle-import:2,15_1,0")
      (libsource (lib "eagle-import") (part "2,15/1,0"))
    )
    (comp (ref "SDA")
      (value "2,15/1,0")
      (footprint "eagle-import:2,15_1,0")
      (libsource (lib "eagle-import") (part "2,15/1,0"))
    )
    (comp (ref "SDA1")
      (value "2,15/1,0")
      (footprint "eagle-import:2,15_1,0")
      (libsource (lib "eagle-import") (part "2,15/1,0"))
    )
    (comp (ref "SDA2")
      (value "2,15/1,0")
      (footprint "eagle-import:2,15_1,0")
      (libsource (lib "eagle-import") (part "2,15/1,0"))
    )
    (comp (ref "SDA3")
      (value "2,15/1,0")
      (footprint "eagle-import:2,15_1,0")
      (libsource (lib "eagle-import") (part "2,15/1,0"))
    )
    (comp (ref "SDA4")
      (value "2,15/1,0")
      (footprint "eagle-import:2,15_1,0")
      (libsource (lib "eagle-import") (part "2,15/1,0"))
    )
    (comp (ref "SDA5")
      (value "2,15/1,0")
      (footprint "eagle-import:2,15_1,0")
      (libsource (lib "eagle-import") (part "2,15/1,0"))
    )
    (comp (ref "SDA6")
      (value "2,15/1,0")
      (footprint "eagle-import:2,15_1,0")
      (libsource (lib "eagle-import") (part "2,15/1,0"))
    )
    (comp (ref "SDA7")
      (value "2,15/1,0")
      (footprint "eagle-import:2,15_1,0")
      (libsource (lib "eagle-import") (part "2,15/1,0"))
    )
    (comp (ref "SDA8")
      (value "2,15/1,0")
      (footprint "eagle-import:2,15_1,0")
      (libsource (lib "eagle-import") (part "2,15/1,0"))
    )
    (comp (ref "SDA9")
      (value "2,15/1,0")
      (footprint "eagle-import:2,15_1,0")
      (libsource (lib "eagle-import") (part "2,15/1,0"))
    )
    (comp (ref "SDA10")
      (value "2,15/1,0")
      (footprint "eagle-import:2,15_1,0")
      (libsource (lib "eagle-import") (part "2,15/1,0"))
    )
    (comp (ref "SDA11")
      (value "2,15/1,0")
      (footprint "eagle-import:2,15_1,0")
      (libsource (lib "eagle-import") (part "2,15/1,0"))
    )
    (comp (ref "SDA12")
      (value "2,15/1,0")
      (footprint "eagle-import:2,15_1,0")
      (libsource (lib "eagle-import") (part "2,15/1,0"))
    )
    (comp (ref "SDA13")
      (value "2,15/1,0")
      (footprint "eagle-import:2,15_1,0")
      (libsource (lib "eagle-import") (part "2,15/1,0"))
    )
    (comp (ref "SDA14")
      (value "2,15/1,0")
      (footprint "eagle-import:2,15_1,0")
      (libsource (lib "eagle-import") (part "2,15/1,0"))
    )
    (comp (ref "SDA15")
      (value "2,15/1,0")
      (footprint "eagle-import:2,15_1,0")
      (libsource (lib "eagle-import") (part "2,15/1,0"))
    )
    (comp (ref "SDA16")
      (value "2,15/1,0")
      (footprint "eagle-import:2,15_1,0")
      (libsource (lib "eagle-import") (part "2,15/1,0"))
    )
    (comp (ref "SDA17")
      (value "2,15/1,0")
      (footprint "eagle-import:2,15_1,0")
      (libsource (lib "eagle-import") (part "2,15/1,0"))
    )
    (comp (ref "SDA18")
      (value "2,15/1,0")
      (footprint "eagle-import:2,15_1,0")
      (libsource (lib "eagle-import") (part "2,15/1,0"))
    )
    (comp (ref "SDA19")
      (value "2,15/1,0")
      (footprint "eagle-import:2,15_1,0")
      (libsource (lib "eagle-import") (part "2,15/1,0"))
    )
    (comp (ref "SDA20")
      (value "2,15/1,0")
      (footprint "eagle-import:2,15_1,0")
      (libsource (lib "eagle-import") (part "2,15/1,0"))
    )
    (comp (ref "SDA21")
      (value "2,15/1,0")
      (footprint "eagle-import:2,15_1,0")
      (libsource (lib "eagle-import") (part "2,15/1,0"))
    )
    (comp (ref "SDA22")
      (value "2,15/1,0")
      (footprint "eagle-import:2,15_1,0")
      (libsource (lib "eagle-import") (part "2,15/1,0"))
    )
    (comp (ref "SDA23")
      (value "2,15/1,0")
      (footprint "eagle-import:2,15_1,0")
      (libsource (lib "eagle-import") (part "2,15/1,0"))
    )
    (comp (ref "SDA24")
      (value "2,15/1,0")
      (footprint "eagle-import:2,15_1,0")
      (libsource (lib "eagle-import") (part "2,15/1,0"))
    )
    (comp (ref "VCC")
      (value "2,15/1,0")
      (footprint "eagle-import:2,15_1,0")
      (libsource (lib "eagle-import") (part "2,15/1,0"))
    )
    (comp (ref "VCC1")
      (value "2,15/1,0")
      (footprint "eagle-import:2,15_1,0")
      (libsource (lib "eagle-import") (part "2,15/1,0"))
    )
    (comp (ref "VCC2")
      (value "2,15/1,0")
      (footprint "eagle-import:2,15_1,0")
      (libsource (lib "eagle-import") (part "2,15/1,0"))
    )
    (comp (ref "VCC3")
      (value "2,15/1,0")
      (footprint "eagle-import:2,15_1,0")
      (libsource (lib "eagle-import") (part "2,15/1,0"))
    )
    (comp (ref "VCC4")
      (value "2,15/1,0")
      (footprint "eagle-import:2,15_1,0")
      (libsource (lib "eagle-import") (part "2,15/1,0"))
    )
    (comp (ref "VCC5")
      (value "2,15/1,0")
      (footprint "eagle-import:2,15_1,0")
      (libsource (lib "eagle-import") (part "2,15/1,0"))
    )
    (comp (ref "VCC6")
      (value "2,15/1,0")
      (footprint "eagle-import:2,15_1,0")
      (libsource (lib "eagle-import") (part "2,15/1,0"))
    )
    (comp (ref "VCC7")
      (value "2,15/1,0")
      (footprint "eagle-import:2,15_1,0")
      (libsource (lib "eagle-import") (part "2,15/1,0"))
    )
    (comp (ref "VCC8")
      (value "2,15/1,0")
      (footprint "eagle-import:2,15_1,0")
      (libsource (lib "eagle-import") (part "2,15/1,0"))
    )
    (comp (ref "VCC9")
      (value "2,15/1,0")
      (footprint "eagle-import:2,15_1,0")
      (libsource (lib "eagle-import") (part "2,15/1,0"))
    )
    (comp (ref "VCC10")
      (value "2,15/1,0")
      (footprint "eagle-import:2,15_1,0")
      (libsource (lib "eagle-import") (part "2,15/1,0"))
    )
    (comp (ref "VCC11")
      (value "2,15/1,0")
      (footprint "eagle-import:2,15_1,0")
      (libsource (lib "eagle-import") (part "2,15/1,0"))
    )
    (comp (ref "VCC12")
      (value "2,15/1,0")
      (footprint "eagle-import:2,15_1,0")
      (libsource (lib "eagle-import") (part "2,15/1,0"))
    )
    (comp (ref "VCC13")
      (value "2,15/1,0")
      (footprint "eagle-import:2,15_1,0")
      (libsource (lib "eagle-import") (part "2,15/1,0"))
    )
    (comp (ref "VCC14")
      (value "2,15/1,0")
      (footprint "eagle-import:2,15_1,0")
      (libsource (lib "eagle-import") (part "2,15/1,0"))
    )
    (comp (ref "VCC15")
      (value "2,15/1,0")
      (footprint "eagle-import:2,15_1,0")
      (libsource (lib "eagle-import") (part "2,15/1,0"))
    )
    (comp (ref "VCC16")
      (value "2,15/1,0")
      (footprint "eagle-import:2,15_1,0")
      (libsource (lib "eagle-import") (part "2,15/1,0"))
    )
    (comp (ref "VCC17")
      (value "2,15/1,0")
      (footprint "eagle-import:2,15_1,0")
      (libsource (lib "eagle-import") (part "2,15/1,0"))
    )
    (comp (ref "VCC18")
      (value "2,15/1,0")
      (footprint "eagle-import:2,15_1,0")
      (libsource (lib "eagle-import") (part "2,15/1,0"))
    )
    (comp (ref "VCC19")
      (value "2,15/1,0")
      (footprint "eagle-import:2,15_1,0")
      (libsource (lib "eagle-import") (part "2,15/1,0"))
    )
    (comp (ref "VCC20")
      (value "2,15/1,0")
      (footprint "eagle-import:2,15_1,0")
      (libsource (lib "eagle-import") (part "2,15/1,0"))
    )
    (comp (ref "VCC21")
      (value "2,15/1,0")
      (footprint "eagle-import:2,15_1,0")
      (libsource (lib "eagle-import") (part "2,15/1,0"))
    )
    (comp (ref "VCC22")
      (value "2,15/1,0")
      (footprint "eagle-import:2,15_1,0")
      (libsource (lib "eagle-import") (part "2,15/1,0"))
    )
    (comp (ref "VCC23")
      (value "2,15/1,0")
      (footprint "eagle-import:2,15_1,0")
      (libsource (lib "eagle-import") (part "2,15/1,0"))
    )
    (comp (ref "VCC24")
      (value "2,15/1,0")
      (footprint "eagle-import:2,15_1,0")
      (libsource (lib "eagle-import") (part "2,15/1,0"))
    )
  )
  (nets
    (net (code "1") (name "5V") (class "Default")
      (node (ref "ARD-5V") (pin "1") (pinfunction "P_1") (pintype "passive"))
      (node (ref "IC1") (pin "18") (pinfunction "VCC_18") (pintype "power_in"))
      (node (ref "IC1") (pin "3") (pinfunction "A2_3") (pintype "input"))
      (node (ref "IC1") (pin "6") (pinfunction "/RST_6") (pintype "input"))
      (node (ref "IC2") (pin "18") (pinfunction "VCC_18") (pintype "power_in"))
      (node (ref "IC2") (pin "4") (pinfunction "A1_4") (pintype "input"))
      (node (ref "IC2") (pin "6") (pinfunction "/RST_6") (pintype "input"))
      (node (ref "IC3") (pin "18") (pinfunction "VCC_18") (pintype "power_in"))
      (node (ref "IC3") (pin "5") (pinfunction "A0_5") (pintype "input"))
      (node (ref "IC3") (pin "6") (pinfunction "/RST_6") (pintype "input"))
      (node (ref "J1") (pin "3") (pinfunction "3_3") (pintype "passive"))
      (node (ref "J10") (pin "3") (pinfunction "3_3") (pintype "passive"))
      (node (ref "J11") (pin "3") (pinfunction "3_3") (pintype "passive"))
      (node (ref "J12") (pin "3") (pinfunction "3_3") (pintype "passive"))
      (node (ref "J13") (pin "3") (pinfunction "3_3") (pintype "passive"))
      (node (ref "J14") (pin "3") (pinfunction "3_3") (pintype "passive"))
      (node (ref "J15") (pin "3") (pinfunction "3_3") (pintype "passive"))
      (node (ref "J16") (pin "3") (pinfunction "3_3") (pintype "passive"))
      (node (ref "J17") (pin "3") (pinfunction "3_3") (pintype "passive"))
      (node (ref "J18") (pin "3") (pinfunction "3_3") (pintype "passive"))
      (node (ref "J19") (pin "3") (pinfunction "3_3") (pintype "passive"))
      (node (ref "J2") (pin "3") (pinfunction "3_3") (pintype "passive"))
      (node (ref "J20") (pin "3") (pinfunction "3_3") (pintype "passive"))
      (node (ref "J21") (pin "3") (pinfunction "3_3") (pintype "passive"))
      (node (ref "J22") (pin "3") (pinfunction "3_3") (pintype "passive"))
      (node (ref "J23") (pin "3") (pinfunction "3_3") (pintype "passive"))
      (node (ref "J24") (pin "3") (pinfunction "3_3") (pintype "passive"))
      (node (ref "J25") (pin "3") (pinfunction "3_3") (pintype "passive"))
      (node (ref "J3") (pin "3") (pinfunction "3_3") (pintype "passive"))
      (node (ref "J4") (pin "3") (pinfunction "3_3") (pintype "passive"))
      (node (ref "J5") (pin "3") (pinfunction "3_3") (pintype "passive"))
      (node (ref "J6") (pin "3") (pinfunction "3_3") (pintype "passive"))
      (node (ref "J7") (pin "3") (pinfunction "3_3") (pintype "passive"))
      (node (ref "J8") (pin "3") (pinfunction "3_3") (pintype "passive"))
      (node (ref "J9") (pin "3") (pinfunction "3_3") (pintype "passive"))
      (node (ref "R1") (pin "P$1") (pinfunction "1_P$1") (pintype "passive"))
      (node (ref "R10") (pin "P$2") (pinfunction "2_P$2") (pintype "passive"))
      (node (ref "R2") (pin "P$1") (pinfunction "1_P$1") (pintype "passive"))
      (node (ref "R3") (pin "P$1") (pinfunction "1_P$1") (pintype "passive"))
      (node (ref "R4") (pin "P$1") (pinfunction "1_P$1") (pintype "passive"))
      (node (ref "R5") (pin "P$1") (pinfunction "1_P$1") (pintype "passive"))
      (node (ref "R6") (pin "P$2") (pinfunction "2_P$2") (pintype "passive"))
      (node (ref "R7") (pin "P$2") (pinfunction "2_P$2") (pintype "passive"))
      (node (ref "R8") (pin "P$2") (pinfunction "2_P$2") (pintype "passive"))
      (node (ref "R9") (pin "P$2") (pinfunction "2_P$2") (pintype "passive"))
    )
    (net (code "2") (name "GND") (class "Default")
      (node (ref "ARD-GND") (pin "1") (pinfunction "P_1") (pintype "passive"))
      (node (ref "GND") (pin "1") (pinfunction "P_1") (pintype "passive"))
      (node (ref "GND1") (pin "1") (pinfunction "P_1") (pintype "passive"))
      (node (ref "GND10") (pin "1") (pinfunction "P_1") (pintype "passive"))
      (node (ref "GND11") (pin "1") (pinfunction "P_1") (pintype "passive"))
      (node (ref "GND12") (pin "1") (pinfunction "P_1") (pintype "passive"))
      (node (ref "GND13") (pin "1") (pinfunction "P_1") (pintype "passive"))
      (node (ref "GND14") (pin "1") (pinfunction "P_1") (pintype "passive"))
      (node (ref "GND15") (pin "1") (pinfunction "P_1") (pintype "passive"))
      (node (ref "GND16") (pin "1") (pinfunction "P_1") (pintype "passive"))
      (node (ref "GND17") (pin "1") (pinfunction "P_1") (pintype "passive"))
      (node (ref "GND18") (pin "1") (pinfunction "P_1") (pintype "passive"))
      (node (ref "GND19") (pin "1") (pinfunction "P_1") (pintype "passive"))
      (node (ref "GND2") (pin "1") (pinfunction "P_1") (pintype "passive"))
      (node (ref "GND20") (pin "1") (pinfunction "P_1") (pintype "passive"))
      (node (ref "GND21") (pin "1") (pinfunction "P_1") (pintype "passive"))
      (node (ref "GND22") (pin "1") (pinfunction "P_1") (pintype "passive"))
      (node (ref "GND23") (pin "1") (pinfunction "P_1") (pintype "passive"))
      (node (ref "GND24") (pin "1") (pinfunction "P_1") (pintype "passive"))
      (node (ref "GND3") (pin "1") (pinfunction "P_1") (pintype "passive"))
      (node (ref "GND4") (pin "1") (pinfunction "P_1") (pintype "passive"))
      (node (ref "GND5") (pin "1") (pinfunction "P_1") (pintype "passive"))
      (node (ref "GND6") (pin "1") (pinfunction "P_1") (pintype "passive"))
      (node (ref "GND7") (pin "1") (pinfunction "P_1") (pintype "passive"))
      (node (ref "GND8") (pin "1") (pinfunction "P_1") (pintype "passive"))
      (node (ref "GND9") (pin "1") (pinfunction "P_1") (pintype "passive"))
      (node (ref "IC1") (pin "4") (pinfunction "A1_4") (pintype "input"))
      (node (ref "IC1") (pin "5") (pinfunction "A0_5") (pintype "input"))
      (node (ref "IC1") (pin "9") (pinfunction "GND_9") (pintype "power_in"))
      (node (ref "IC2") (pin "3") (pinfunction "A2_3") (pintype "input"))
      (node (ref "IC2") (pin "5") (pinfunction "A0_5") (pintype "input"))
      (node (ref "IC2") (pin "9") (pinfunction "GND_9") (pintype "power_in"))
      (node (ref "IC3") (pin "3") (pinfunction "A2_3") (pintype "input"))
      (node (ref "IC3") (pin "4") (pinfunction "A1_4") (pintype "input"))
      (node (ref "IC3") (pin "9") (pinfunction "GND_9") (pintype "power_in"))
      (node (ref "J1") (pin "2") (pinfunction "2_2") (pintype "passive"))
      (node (ref "J10") (pin "2") (pinfunction "2_2") (pintype "passive"))
      (node (ref "J11") (pin "2") (pinfunction "2_2") (pintype "passive"))
      (node (ref "J12") (pin "2") (pinfunction "2_2") (pintype "passive"))
      (node (ref "J13") (pin "2") (pinfunction "2_2") (pintype "passive"))
      (node (ref "J14") (pin "2") (pinfunction "2_2") (pintype "passive"))
      (node (ref "J15") (pin "2") (pinfunction "2_2") (pintype "passive"))
      (node (ref "J16") (pin "2") (pinfunction "2_2") (pintype "passive"))
      (node (ref "J17") (pin "2") (pinfunction "2_2") (pintype "passive"))
      (node (ref "J18") (pin "2") (pinfunction "2_2") (pintype "passive"))
      (node (ref "J19") (pin "2") (pinfunction "2_2") (pintype "passive"))
      (node (ref "J2") (pin "2") (pinfunction "2_2") (pintype "passive"))
      (node (ref "J20") (pin "2") (pinfunction "2_2") (pintype "passive"))
      (node (ref "J21") (pin "2") (pinfunction "2_2") (pintype "passive"))
      (node (ref "J22") (pin "2") (pinfunction "2_2") (pintype "passive"))
      (node (ref "J23") (pin "2") (pinfunction "2_2") (pintype "passive"))
      (node (ref "J24") (pin "2") (pinfunction "2_2") (pintype "passive"))
      (node (ref "J25") (pin "2") (pinfunction "2_2") (pintype "passive"))
      (node (ref "J3") (pin "2") (pinfunction "2_2") (pintype "passive"))
      (node (ref "J4") (pin "2") (pinfunction "2_2") (pintype "passive"))
      (node (ref "J5") (pin "2") (pinfunction "2_2") (pintype "passive"))
      (node (ref "J6") (pin "2") (pinfunction "2_2") (pintype "passive"))
      (node (ref "J7") (pin "2") (pinfunction "2_2") (pintype "passive"))
      (node (ref "J8") (pin "2") (pinfunction "2_2") (pintype "passive"))
      (node (ref "J9") (pin "2") (pinfunction "2_2") (pintype "passive"))
      (node (ref "PAD11") (pin "1") (pinfunction "P_1") (pintype "passive"))
      (node (ref "PAD15") (pin "1") (pinfunction "P_1") (pintype "passive"))
      (node (ref "PAD19") (pin "1") (pinfunction "P_1") (pintype "passive"))
      (node (ref "PAD23") (pin "1") (pinfunction "P_1") (pintype "passive"))
      (node (ref "PAD27") (pin "1") (pinfunction "P_1") (pintype "passive"))
      (node (ref "PAD3") (pin "1") (pinfunction "P_1") (pintype "passive"))
      (node (ref "PAD31") (pin "1") (pinfunction "P_1") (pintype "passive"))
      (node (ref "PAD35") (pin "1") (pinfunction "P_1") (pintype "passive"))
      (node (ref "PAD39") (pin "1") (pinfunction "P_1") (pintype "passive"))
      (node (ref "PAD43") (pin "1") (pinfunction "P_1") (pintype "passive"))
      (node (ref "PAD47") (pin "1") (pinfunction "P_1") (pintype "passive"))
      (node (ref "PAD51") (pin "1") (pinfunction "P_1") (pintype "passive"))
      (node (ref "PAD55") (pin "1") (pinfunction "P_1") (pintype "passive"))
      (node (ref "PAD59") (pin "1") (pinfunction "P_1") (pintype "passive"))
      (node (ref "PAD63") (pin "1") (pinfunction "P_1") (pintype "passive"))
      (node (ref "PAD67") (pin "1") (pinfunction "P_1") (pintype "passive"))
      (node (ref "PAD7") (pin "1") (pinfunction "P_1") (pintype "passive"))
      (node (ref "PAD71") (pin "1") (pinfunction "P_1") (pintype "passive"))
      (node (ref "PAD75") (pin "1") (pinfunction "P_1") (pintype "passive"))
      (node (ref "PAD79") (pin "1") (pinfunction "P_1") (pintype "passive"))
      (node (ref "PAD83") (pin "1") (pinfunction "P_1") (pintype "passive"))
      (node (ref "PAD87") (pin "1") (pinfunction "P_1") (pintype "passive"))
      (node (ref "PAD91") (pin "1") (pinfunction "P_1") (pintype "passive"))
      (node (ref "PAD95") (pin "1") (pinfunction "P_1") (pintype "passive"))
      (node (ref "PAD99") (pin "1") (pinfunction "P_1") (pintype "passive"))
    )
    (net (code "3") (name "GPIO1") (class "Default")
      (node (ref "J1") (pin "1") (pinfunction "1_1") (pintype "passive"))
      (node (ref "R27") (pin "P$2") (pinfunction "2_P$2") (pintype "passive"))
    )
    (net (code "4") (name "GPIO2") (class "Default")
      (node (ref "J2") (pin "1") (pinfunction "1_1") (pintype "passive"))
      (node (ref "R28") (pin "P$2") (pinfunction "2_P$2") (pintype "passive"))
    )
    (net (code "5") (name "GPIO3") (class "Default")
      (node (ref "J3") (pin "1") (pinfunction "1_1") (pintype "passive"))
      (node (ref "R29") (pin "P$2") (pinfunction "2_P$2") (pintype "passive"))
    )
    (net (code "6") (name "GPIO4") (class "Default")
      (node (ref "J4") (pin "1") (pinfunction "1_1") (pintype "passive"))
      (node (ref "R30") (pin "P$2") (pinfunction "2_P$2") (pintype "passive"))
    )
    (net (code "7") (name "GPIO5") (class "Default")
      (node (ref "J5") (pin "1") (pinfunction "1_1") (pintype "passive"))
      (node (ref "R31") (pin "P$2") (pinfunction "2_P$2") (pintype "passive"))
    )
    (net (code "8") (name "GPIO6") (class "Default")
      (node (ref "J6") (pin "1") (pinfunction "1_1") (pintype "passive"))
      (node (ref "R33") (pin "P$2") (pinfunction "2_P$2") (pintype "passive"))
    )
    (net (code "9") (name "GPIO7") (class "Default")
      (node (ref "J7") (pin "1") (pinfunction "1_1") (pintype "passive"))
      (node (ref "R32") (pin "P$2") (pinfunction "2_P$2") (pintype "passive"))
    )
    (net (code "10") (name "GPIO8") (class "Default")
      (node (ref "J8") (pin "1") (pinfunction "1_1") (pintype "passive"))
      (node (ref "R34") (pin "P$2") (pinfunction "2_P$2") (pintype "passive"))
    )
    (net (code "11") (name "GPIO9") (class "Default")
      (node (ref "J9") (pin "1") (pinfunction "1_1") (pintype "passive"))
      (node (ref "R11") (pin "P$2") (pinfunction "2_P$2") (pintype "passive"))
    )
    (net (code "12") (name "GPIO10") (class "Default")
      (node (ref "J10") (pin "1") (pinfunction "1_1") (pintype "passive"))
      (node (ref "R12") (pin "P$2") (pinfunction "2_P$2") (pintype "passive"))
    )
    (net (code "13") (name "GPIO11") (class "Default")
      (node (ref "J11") (pin "1") (pinfunction "1_1") (pintype "passive"))
      (node (ref "R13") (pin "P$2") (pinfunction "2_P$2") (pintype "passive"))
    )
    (net (code "14") (name "GPIO12") (class "Default")
      (node (ref "J12") (pin "1") (pinfunction "1_1") (pintype "passive"))
      (node (ref "R14") (pin "P$2") (pinfunction "2_P$2") (pintype "passive"))
    )
    (net (code "15") (name "GPIO13") (class "Default")
      (node (ref "J13") (pin "1") (pinfunction "1_1") (pintype "passive"))
      (node (ref "R15") (pin "P$2") (pinfunction "2_P$2") (pintype "passive"))
    )
    (net (code "16") (name "GPIO14") (class "Default")
      (node (ref "J14") (pin "1") (pinfunction "1_1") (pintype "passive"))
      (node (ref "R16") (pin "P$2") (pinfunction "2_P$2") (pintype "passive"))
    )
    (net (code "17") (name "GPIO15") (class "Default")
      (node (ref "J15") (pin "1") (pinfunction "1_1") (pintype "passive"))
      (node (ref "R17") (pin "P$2") (pinfunction "2_P$2") (pintype "passive"))
    )
    (net (code "18") (name "GPIO16") (class "Default")
      (node (ref "J16") (pin "1") (pinfunction "1_1") (pintype "passive"))
      (node (ref "R18") (pin "P$2") (pinfunction "2_P$2") (pintype "passive"))
    )
    (net (code "19") (name "GPIO17") (class "Default")
      (node (ref "J17") (pin "1") (pinfunction "1_1") (pintype "passive"))
      (node (ref "R19") (pin "P$2") (pinfunction "2_P$2") (pintype "passive"))
    )
    (net (code "20") (name "GPIO18") (class "Default")
      (node (ref "J18") (pin "1") (pinfunction "1_1") (pintype "passive"))
      (node (ref "R20") (pin "P$2") (pinfunction "2_P$2") (pintype "passive"))
    )
    (net (code "21") (name "GPIO19") (class "Default")
      (node (ref "J19") (pin "1") (pinfunction "1_1") (pintype "passive"))
      (node (ref "R21") (pin "P$2") (pinfunction "2_P$2") (pintype "passive"))
    )
    (net (code "22") (name "GPIO20") (class "Default")
      (node (ref "J20") (pin "1") (pinfunction "1_1") (pintype "passive"))
      (node (ref "R22") (pin "P$2") (pinfunction "2_P$2") (pintype "passive"))
    )
    (net (code "23") (name "GPIO21") (class "Default")
      (node (ref "J21") (pin "1") (pinfunction "1_1") (pintype "passive"))
      (node (ref "R23") (pin "P$2") (pinfunction "2_P$2") (pintype "passive"))
    )
    (net (code "24") (name "GPIO22") (class "Default")
      (node (ref "J22") (pin "1") (pinfunction "1_1") (pintype "passive"))
      (node (ref "R24") (pin "P$2") (pinfunction "2_P$2") (pintype "passive"))
    )
    (net (code "25") (name "GPIO23") (class "Default")
      (node (ref "J23") (pin "1") (pinfunction "1_1") (pintype "passive"))
      (node (ref "R25") (pin "P$2") (pinfunction "2_P$2") (pintype "passive"))
    )
    (net (code "26") (name "GPIO24") (class "Default")
      (node (ref "J24") (pin "1") (pinfunction "1_1") (pintype "passive"))
      (node (ref "R26") (pin "P$2") (pinfunction "2_P$2") (pintype "passive"))
    )
    (net (code "27") (name "GPIO25") (class "Default")
      (node (ref "ARD-DIG-PIN") (pin "1") (pinfunction "P_1") (pintype "passive"))
      (node (ref "J25") (pin "1") (pinfunction "1_1") (pintype "passive"))
    )
    (net (code "28") (name "N$2") (class "Default")
      (node (ref "IC1") (pin "8") (pinfunction "INT_8") (pintype "output"))
    )
    (net (code "29") (name "N$29") (class "Default")
      (node (ref "IC2") (pin "8") (pinfunction "INT_8") (pintype "output"))
    )
    (net (code "30") (name "N$36") (class "Default")
      (node (ref "IC3") (pin "8") (pinfunction "INT_8") (pintype "output"))
    )
    (net (code "31") (name "Net-(IC1-GP0)") (class "Default")
      (node (ref "IC1") (pin "10") (pinfunction "GP0_10") (pintype "bidirectional"))
      (node (ref "R27") (pin "P$1") (pinfunction "1_P$1") (pintype "passive"))
    )
    (net (code "32") (name "Net-(IC1-GP1)") (class "Default")
      (node (ref "IC1") (pin "11") (pinfunction "GP1_11") (pintype "bidirectional"))
      (node (ref "R28") (pin "P$1") (pinfunction "1_P$1") (pintype "passive"))
    )
    (net (code "33") (name "Net-(IC1-GP2)") (class "Default")
      (node (ref "IC1") (pin "12") (pinfunction "GP2_12") (pintype "bidirectional"))
      (node (ref "R29") (pin "P$1") (pinfunction "1_P$1") (pintype "passive"))
    )
    (net (code "34") (name "Net-(IC1-GP3)") (class "Default")
      (node (ref "IC1") (pin "13") (pinfunction "GP3_13") (pintype "bidirectional"))
      (node (ref "R30") (pin "P$1") (pinfunction "1_P$1") (pintype "passive"))
    )
    (net (code "35") (name "Net-(IC1-GP4)") (class "Default")
      (node (ref "IC1") (pin "14") (pinfunction "GP4_14") (pintype "bidirectional"))
      (node (ref "R31") (pin "P$1") (pinfunction "1_P$1") (pintype "passive"))
    )
    (net (code "36") (name "Net-(IC1-GP5)") (class "Default")
      (node (ref "IC1") (pin "15") (pinfunction "GP5_15") (pintype "bidirectional"))
      (node (ref "R33") (pin "P$1") (pinfunction "1_P$1") (pintype "passive"))
    )
    (net (code "37") (name "Net-(IC1-GP6)") (class "Default")
      (node (ref "IC1") (pin "16") (pinfunction "GP6_16") (pintype "bidirectional"))
      (node (ref "R32") (pin "P$1") (pinfunction "1_P$1") (pintype "passive"))
    )
    (net (code "38") (name "Net-(IC1-GP7)") (class "Default")
      (node (ref "IC1") (pin "17") (pinfunction "GP7_17") (pintype "bidirectional"))
      (node (ref "R34") (pin "P$1") (pinfunction "1_P$1") (pintype "passive"))
    )
    (net (code "39") (name "Net-(IC2-GP0)") (class "Default")
      (node (ref "IC2") (pin "10") (pinfunction "GP0_10") (pintype "bidirectional"))
      (node (ref "R11") (pin "P$1") (pinfunction "1_P$1") (pintype "passive"))
    )
    (net (code "40") (name "Net-(IC2-GP1)") (class "Default")
      (node (ref "IC2") (pin "11") (pinfunction "GP1_11") (pintype "bidirectional"))
      (node (ref "R12") (pin "P$1") (pinfunction "1_P$1") (pintype "passive"))
    )
    (net (code "41") (name "Net-(IC2-GP2)") (class "Default")
      (node (ref "IC2") (pin "12") (pinfunction "GP2_12") (pintype "bidirectional"))
      (node (ref "R13") (pin "P$1") (pinfunction "1_P$1") (pintype "passive"))
    )
    (net (code "42") (name "Net-(IC2-GP3)") (class "Default")
      (node (ref "IC2") (pin "13") (pinfunction "GP3_13") (pintype "bidirectional"))
      (node (ref "R14") (pin "P$1") (pinfunction "1_P$1") (pintype "passive"))
    )
    (net (code "43") (name "Net-(IC2-GP4)") (class "Default")
      (node (ref "IC2") (pin "14") (pinfunction "GP4_14") (pintype "bidirectional"))
      (node (ref "R15") (pin "P$1") (pinfunction "1_P$1") (pintype "passive"))
    )
    (net (code "44") (name "Net-(IC2-GP5)") (class "Default")
      (node (ref "IC2") (pin "15") (pinfunction "GP5_15") (pintype "bidirectional"))
      (node (ref "R16") (pin "P$1") (pinfunction "1_P$1") (pintype "passive"))
    )
    (net (code "45") (name "Net-(IC2-GP6)") (class "Default")
      (node (ref "IC2") (pin "16") (pinfunction "GP6_16") (pintype "bidirectional"))
      (node (ref "R17") (pin "P$1") (pinfunction "1_P$1") (pintype "passive"))
    )
    (net (code "46") (name "Net-(IC2-GP7)") (class "Default")
      (node (ref "IC2") (pin "17") (pinfunction "GP7_17") (pintype "bidirectional"))
      (node (ref "R18") (pin "P$1") (pinfunction "1_P$1") (pintype "passive"))
    )
    (net (code "47") (name "Net-(IC3-GP0)") (class "Default")
      (node (ref "IC3") (pin "10") (pinfunction "GP0_10") (pintype "bidirectional"))
      (node (ref "R19") (pin "P$1") (pinfunction "1_P$1") (pintype "passive"))
    )
    (net (code "48") (name "Net-(IC3-GP1)") (class "Default")
      (node (ref "IC3") (pin "11") (pinfunction "GP1_11") (pintype "bidirectional"))
      (node (ref "R20") (pin "P$1") (pinfunction "1_P$1") (pintype "passive"))
    )
    (net (code "49") (name "Net-(IC3-GP2)") (class "Default")
      (node (ref "IC3") (pin "12") (pinfunction "GP2_12") (pintype "bidirectional"))
      (node (ref "R21") (pin "P$1") (pinfunction "1_P$1") (pintype "passive"))
    )
    (net (code "50") (name "Net-(IC3-GP3)") (class "Default")
      (node (ref "IC3") (pin "13") (pinfunction "GP3_13") (pintype "bidirectional"))
      (node (ref "R22") (pin "P$1") (pinfunction "1_P$1") (pintype "passive"))
    )
    (net (code "51") (name "Net-(IC3-GP4)") (class "Default")
      (node (ref "IC3") (pin "14") (pinfunction "GP4_14") (pintype "bidirectional"))
      (node (ref "R23") (pin "P$1") (pinfunction "1_P$1") (pintype "passive"))
    )
    (net (code "52") (name "Net-(IC3-GP5)") (class "Default")
      (node (ref "IC3") (pin "15") (pinfunction "GP5_15") (pintype "bidirectional"))
      (node (ref "R24") (pin "P$1") (pinfunction "1_P$1") (pintype "passive"))
    )
    (net (code "53") (name "Net-(IC3-GP6)") (class "Default")
      (node (ref "IC3") (pin "16") (pinfunction "GP6_16") (pintype "bidirectional"))
      (node (ref "R25") (pin "P$1") (pinfunction "1_P$1") (pintype "passive"))
    )
    (net (code "54") (name "Net-(IC3-GP7)") (class "Default")
      (node (ref "IC3") (pin "17") (pinfunction "GP7_17") (pintype "bidirectional"))
      (node (ref "R26") (pin "P$1") (pinfunction "1_P$1") (pintype "passive"))
    )
    (net (code "55") (name "SCL") (class "Default")
      (node (ref "ARD-SCL") (pin "1") (pinfunction "P_1") (pintype "passive"))
      (node (ref "IC1") (pin "1") (pinfunction "SCL_1") (pintype "bidirectional"))
      (node (ref "IC2") (pin "1") (pinfunction "SCL_1") (pintype "bidirectional"))
      (node (ref "IC3") (pin "1") (pinfunction "SCL_1") (pintype "bidirectional"))
      (node (ref "PAD10") (pin "1") (pinfunction "P_1") (pintype "passive"))
      (node (ref "PAD14") (pin "1") (pinfunction "P_1") (pintype "passive"))
      (node (ref "PAD18") (pin "1") (pinfunction "P_1") (pintype "passive"))
      (node (ref "PAD2") (pin "1") (pinfunction "P_1") (pintype "passive"))
      (node (ref "PAD22") (pin "1") (pinfunction "P_1") (pintype "passive"))
      (node (ref "PAD26") (pin "1") (pinfunction "P_1") (pintype "passive"))
      (node (ref "PAD30") (pin "1") (pinfunction "P_1") (pintype "passive"))
      (node (ref "PAD34") (pin "1") (pinfunction "P_1") (pintype "passive"))
      (node (ref "PAD38") (pin "1") (pinfunction "P_1") (pintype "passive"))
      (node (ref "PAD42") (pin "1") (pinfunction "P_1") (pintype "passive"))
      (node (ref "PAD46") (pin "1") (pinfunction "P_1") (pintype "passive"))
      (node (ref "PAD50") (pin "1") (pinfunction "P_1") (pintype "passive"))
      (node (ref "PAD54") (pin "1") (pinfunction "P_1") (pintype "passive"))
      (node (ref "PAD58") (pin "1") (pinfunction "P_1") (pintype "passive"))
      (node (ref "PAD6") (pin "1") (pinfunction "P_1") (pintype "passive"))
      (node (ref "PAD62") (pin "1") (pinfunction "P_1") (pintype "passive"))
      (node (ref "PAD66") (pin "1") (pinfunction "P_1") (pintype "passive"))
      (node (ref "PAD70") (pin "1") (pinfunction "P_1") (pintype "passive"))
      (node (ref "PAD74") (pin "1") (pinfunction "P_1") (pintype "passive"))
      (node (ref "PAD78") (pin "1") (pinfunction "P_1") (pintype "passive"))
      (node (ref "PAD82") (pin "1") (pinfunction "P_1") (pintype "passive"))
      (node (ref "PAD86") (pin "1") (pinfunction "P_1") (pintype "passive"))
      (node (ref "PAD90") (pin "1") (pinfunction "P_1") (pintype "passive"))
      (node (ref "PAD94") (pin "1") (pinfunction "P_1") (pintype "passive"))
      (node (ref "PAD98") (pin "1") (pinfunction "P_1") (pintype "passive"))
      (node (ref "R1") (pin "P$2") (pinfunction "2_P$2") (pintype "passive"))
      (node (ref "R2") (pin "P$2") (pinfunction "2_P$2") (pintype "passive"))
      (node (ref "R3") (pin "P$2") (pinfunction "2_P$2") (pintype "passive"))
      (node (ref "R4") (pin "P$2") (pinfunction "2_P$2") (pintype "passive"))
      (node (ref "R5") (pin "P$2") (pinfunction "2_P$2") (pintype "passive"))
      (node (ref "SCL") (pin "1") (pinfunction "P_1") (pintype "passive"))
      (node (ref "SCL1") (pin "1") (pinfunction "P_1") (pintype "passive"))
      (node (ref "SCL10") (pin "1") (pinfunction "P_1") (pintype "passive"))
      (node (ref "SCL11") (pin "1") (pinfunction "P_1") (pintype "passive"))
      (node (ref "SCL12") (pin "1") (pinfunction "P_1") (pintype "passive"))
      (node (ref "SCL13") (pin "1") (pinfunction "P_1") (pintype "passive"))
      (node (ref "SCL14") (pin "1") (pinfunction "P_1") (pintype "passive"))
      (node (ref "SCL15") (pin "1") (pinfunction "P_1") (pintype "passive"))
      (node (ref "SCL16") (pin "1") (pinfunction "P_1") (pintype "passive"))
      (node (ref "SCL17") (pin "1") (pinfunction "P_1") (pintype "passive"))
      (node (ref "SCL18") (pin "1") (pinfunction "P_1") (pintype "passive"))
      (node (ref "SCL19") (pin "1") (pinfunction "P_1") (pintype "passive"))
      (node (ref "SCL2") (pin "1") (pinfunction "P_1") (pintype "passive"))
      (node (ref "SCL20") (pin "1") (pinfunction "P_1") (pintype "passive"))
      (node (ref "SCL21") (pin "1") (pinfunction "P_1") (pintype "passive"))
      (node (ref "SCL22") (pin "1") (pinfunction "P_1") (pintype "passive"))
      (node (ref "SCL23") (pin "1") (pinfunction "P_1") (pintype "passive"))
      (node (ref "SCL24") (pin "1") (pinfunction "P_1") (pintype "passive"))
      (node (ref "SCL3") (pin "1") (pinfunction "P_1") (pintype "passive"))
      (node (ref "SCL4") (pin "1") (pinfunction "P_1") (pintype "passive"))
      (node (ref "SCL5") (pin "1") (pinfunction "P_1") (pintype "passive"))
      (node (ref "SCL6") (pin "1") (pinfunction "P_1") (pintype "passive"))
      (node (ref "SCL7") (pin "1") (pinfunction "P_1") (pintype "passive"))
      (node (ref "SCL8") (pin "1") (pinfunction "P_1") (pintype "passive"))
      (node (ref "SCL9") (pin "1") (pinfunction "P_1") (pintype "passive"))
    )
    (net (code "56") (name "SDA") (class "Default")
      (node (ref "ARD-SDA") (pin "1") (pinfunction "P_1") (pintype "passive"))
      (node (ref "IC1") (pin "2") (pinfunction "SDA_2") (pintype "bidirectional"))
      (node (ref "IC2") (pin "2") (pinfunction "SDA_2") (pintype "bidirectional"))
      (node (ref "IC3") (pin "2") (pinfunction "SDA_2") (pintype "bidirectional"))
      (node (ref "PAD100") (pin "1") (pinfunction "P_1") (pintype "passive"))
      (node (ref "PAD12") (pin "1") (pinfunction "P_1") (pintype "passive"))
      (node (ref "PAD16") (pin "1") (pinfunction "P_1") (pintype "passive"))
      (node (ref "PAD20") (pin "1") (pinfunction "P_1") (pintype "passive"))
      (node (ref "PAD24") (pin "1") (pinfunction "P_1") (pintype "passive"))
      (node (ref "PAD28") (pin "1") (pinfunction "P_1") (pintype "passive"))
      (node (ref "PAD32") (pin "1") (pinfunction "P_1") (pintype "passive"))
      (node (ref "PAD36") (pin "1") (pinfunction "P_1") (pintype "passive"))
      (node (ref "PAD4") (pin "1") (pinfunction "P_1") (pintype "passive"))
      (node (ref "PAD40") (pin "1") (pinfunction "P_1") (pintype "passive"))
      (node (ref "PAD44") (pin "1") (pinfunction "P_1") (pintype "passive"))
      (node (ref "PAD48") (pin "1") (pinfunction "P_1") (pintype "passive"))
      (node (ref "PAD52") (pin "1") (pinfunction "P_1") (pintype "passive"))
      (node (ref "PAD56") (pin "1") (pinfunction "P_1") (pintype "passive"))
      (node (ref "PAD60") (pin "1") (pinfunction "P_1") (pintype "passive"))
      (node (ref "PAD64") (pin "1") (pinfunction "P_1") (pintype "passive"))
      (node (ref "PAD68") (pin "1") (pinfunction "P_1") (pintype "passive"))
      (node (ref "PAD72") (pin "1") (pinfunction "P_1") (pintype "passive"))
      (node (ref "PAD76") (pin "1") (pinfunction "P_1") (pintype "passive"))
      (node (ref "PAD8") (pin "1") (pinfunction "P_1") (pintype "passive"))
      (node (ref "PAD80") (pin "1") (pinfunction "P_1") (pintype "passive"))
      (node (ref "PAD84") (pin "1") (pinfunction "P_1") (pintype "passive"))
      (node (ref "PAD88") (pin "1") (pinfunction "P_1") (pintype "passive"))
      (node (ref "PAD92") (pin "1") (pinfunction "P_1") (pintype "passive"))
      (node (ref "PAD96") (pin "1") (pinfunction "P_1") (pintype "passive"))
      (node (ref "R10") (pin "P$1") (pinfunction "1_P$1") (pintype "passive"))
      (node (ref "R6") (pin "P$1") (pinfunction "1_P$1") (pintype "passive"))
      (node (ref "R7") (pin "P$1") (pinfunction "1_P$1") (pintype "passive"))
      (node (ref "R8") (pin "P$1") (pinfunction "1_P$1") (pintype "passive"))
      (node (ref "R9") (pin "P$1") (pinfunction "1_P$1") (pintype "passive"))
      (node (ref "SDA") (pin "1") (pinfunction "P_1") (pintype "passive"))
      (node (ref "SDA1") (pin "1") (pinfunction "P_1") (pintype "passive"))
      (node (ref "SDA10") (pin "1") (pinfunction "P_1") (pintype "passive"))
      (node (ref "SDA11") (pin "1") (pinfunction "P_1") (pintype "passive"))
      (node (ref "SDA12") (pin "1") (pinfunction "P_1") (pintype "passive"))
      (node (ref "SDA13") (pin "1") (pinfunction "P_1") (pintype "passive"))
      (node (ref "SDA14") (pin "1") (pinfunction "P_1") (pintype "passive"))
      (node (ref "SDA15") (pin "1") (pinfunction "P_1") (pintype "passive"))
      (node (ref "SDA16") (pin "1") (pinfunction "P_1") (pintype "passive"))
      (node (ref "SDA17") (pin "1") (pinfunction "P_1") (pintype "passive"))
      (node (ref "SDA18") (pin "1") (pinfunction "P_1") (pintype "passive"))
      (node (ref "SDA19") (pin "1") (pinfunction "P_1") (pintype "passive"))
      (node (ref "SDA2") (pin "1") (pinfunction "P_1") (pintype "passive"))
      (node (ref "SDA20") (pin "1") (pinfunction "P_1") (pintype "passive"))
      (node (ref "SDA21") (pin "1") (pinfunction "P_1") (pintype "passive"))
      (node (ref "SDA22") (pin "1") (pinfunction "P_1") (pintype "passive"))
      (node (ref "SDA23") (pin "1") (pinfunction "P_1") (pintype "passive"))
      (node (ref "SDA24") (pin "1") (pinfunction "P_1") (pintype "passive"))
      (node (ref "SDA3") (pin "1") (pinfunction "P_1") (pintype "passive"))
      (node (ref "SDA4") (pin "1") (pinfunction "P_1") (pintype "passive"))
      (node (ref "SDA5") (pin "1") (pinfunction "P_1") (pintype "passive"))
      (node (ref "SDA6") (pin "1") (pinfunction "P_1") (pintype "passive"))
      (node (ref "SDA7") (pin "1") (pinfunction "P_1") (pintype "passive"))
      (node (ref "SDA8") (pin "1") (pinfunction "P_1") (pintype "passive"))
      (node (ref "SDA9") (pin "1") (pinfunction "P_1") (pintype "passive"))
    )
    (net (code "57") (name "VCC") (class "Default")
      (node (ref "ARD-VCC") (pin "1") (pinfunction "P_1") (pintype "passive"))
      (node (ref "PAD1") (pin "1") (pinfunction "P_1") (pintype "passive"))
      (node (ref "PAD13") (pin "1") (pinfunction "P_1") (pintype "passive"))
      (node (ref "PAD17") (pin "1") (pinfunction "P_1") (pintype "passive"))
      (node (ref "PAD21") (pin "1") (pinfunction "P_1") (pintype "passive"))
      (node (ref "PAD25") (pin "1") (pinfunction "P_1") (pintype "passive"))
      (node (ref "PAD29") (pin "1") (pinfunction "P_1") (pintype "passive"))
      (node (ref "PAD33") (pin "1") (pinfunction "P_1") (pintype "passive"))
      (node (ref "PAD37") (pin "1") (pinfunction "P_1") (pintype "passive"))
      (node (ref "PAD41") (pin "1") (pinfunction "P_1") (pintype "passive"))
      (node (ref "PAD45") (pin "1") (pinfunction "P_1") (pintype "passive"))
      (node (ref "PAD49") (pin "1") (pinfunction "P_1") (pintype "passive"))
      (node (ref "PAD5") (pin "1") (pinfunction "P_1") (pintype "passive"))
      (node (ref "PAD53") (pin "1") (pinfunction "P_1") (pintype "passive"))
      (node (ref "PAD57") (pin "1") (pinfunction "P_1") (pintype "passive"))
      (node (ref "PAD61") (pin "1") (pinfunction "P_1") (pintype "passive"))
      (node (ref "PAD65") (pin "1") (pinfunction "P_1") (pintype "passive"))
      (node (ref "PAD69") (pin "1") (pinfunction "P_1") (pintype "passive"))
      (node (ref "PAD73") (pin "1") (pinfunction "P_1") (pintype "passive"))
      (node (ref "PAD77") (pin "1") (pinfunction "P_1") (pintype "passive"))
      (node (ref "PAD81") (pin "1") (pinfunction "P_1") (pintype "passive"))
      (node (ref "PAD85") (pin "1") (pinfunction "P_1") (pintype "passive"))
      (node (ref "PAD89") (pin "1") (pinfunction "P_1") (pintype "passive"))
      (node (ref "PAD9") (pin "1") (pinfunction "P_1") (pintype "passive"))
      (node (ref "PAD93") (pin "1") (pinfunction "P_1") (pintype "passive"))
      (node (ref "PAD97") (pin "1") (pinfunction "P_1") (pintype "passive"))
      (node (ref "VCC") (pin "1") (pinfunction "P_1") (pintype "passive"))
      (node (ref "VCC1") (pin "1") (pinfunction "P_1") (pintype "passive"))
      (node (ref "VCC10") (pin "1") (pinfunction "P_1") (pintype "passive"))
      (node (ref "VCC11") (pin "1") (pinfunction "P_1") (pintype "passive"))
      (node (ref "VCC12") (pin "1") (pinfunction "P_1") (pintype "passive"))
      (node (ref "VCC13") (pin "1") (pinfunction "P_1") (pintype "passive"))
      (node (ref "VCC14") (pin "1") (pinfunction "P_1") (pintype "passive"))
      (node (ref "VCC15") (pin "1") (pinfunction "P_1") (pintype "passive"))
      (node (ref "VCC16") (pin "1") (pinfunction "P_1") (pintype "passive"))
      (node (ref "VCC17") (pin "1") (pinfunction "P_1") (pintype "passive"))
      (node (ref "VCC18") (pin "1") (pinfunction "P_1") (pintype "passive"))
      (node (ref "VCC19") (pin "1") (pinfunction "P_1") (pintype "passive"))
      (node (ref "VCC2") (pin "1") (pinfunction "P_1") (pintype "passive"))
      (node (ref "VCC20") (pin "1") (pinfunction "P_1") (pintype "passive"))
      (node (ref "VCC21") (pin "1") (pinfunction "P_1") (pintype "passive"))
      (node (ref "VCC22") (pin "1") (pinfunction "P_1") (pintype "passive"))
      (node (ref "VCC23") (pin "1") (pinfunction "P_1") (pintype "passive"))
      (node (ref "VCC24") (pin "1") (pinfunction "P_1") (pintype "passive"))
      (node (ref "VCC3") (pin "1") (pinfunction "P_1") (pintype "passive"))
      (node (ref "VCC4") (pin "1") (pinfunction "P_1") (pintype "passive"))
      (node (ref "VCC5") (pin "1") (pinfunction "P_1") (pintype "passive"))
      (node (ref "VCC6") (pin "1") (pinfunction "P_1") (pintype "passive"))
      (node (ref "VCC7") (pin "1") (pinfunction "P_1") (pintype "passive"))
      (node (ref "VCC8") (pin "1") (pinfunction "P_1") (pintype "passive"))
      (node (ref "VCC9") (pin "1") (pinfunction "P_1") (pintype "passive"))
    )
  )
)
